# -V5.net
KiCad netlist of a schematic drawn in Altium Designer
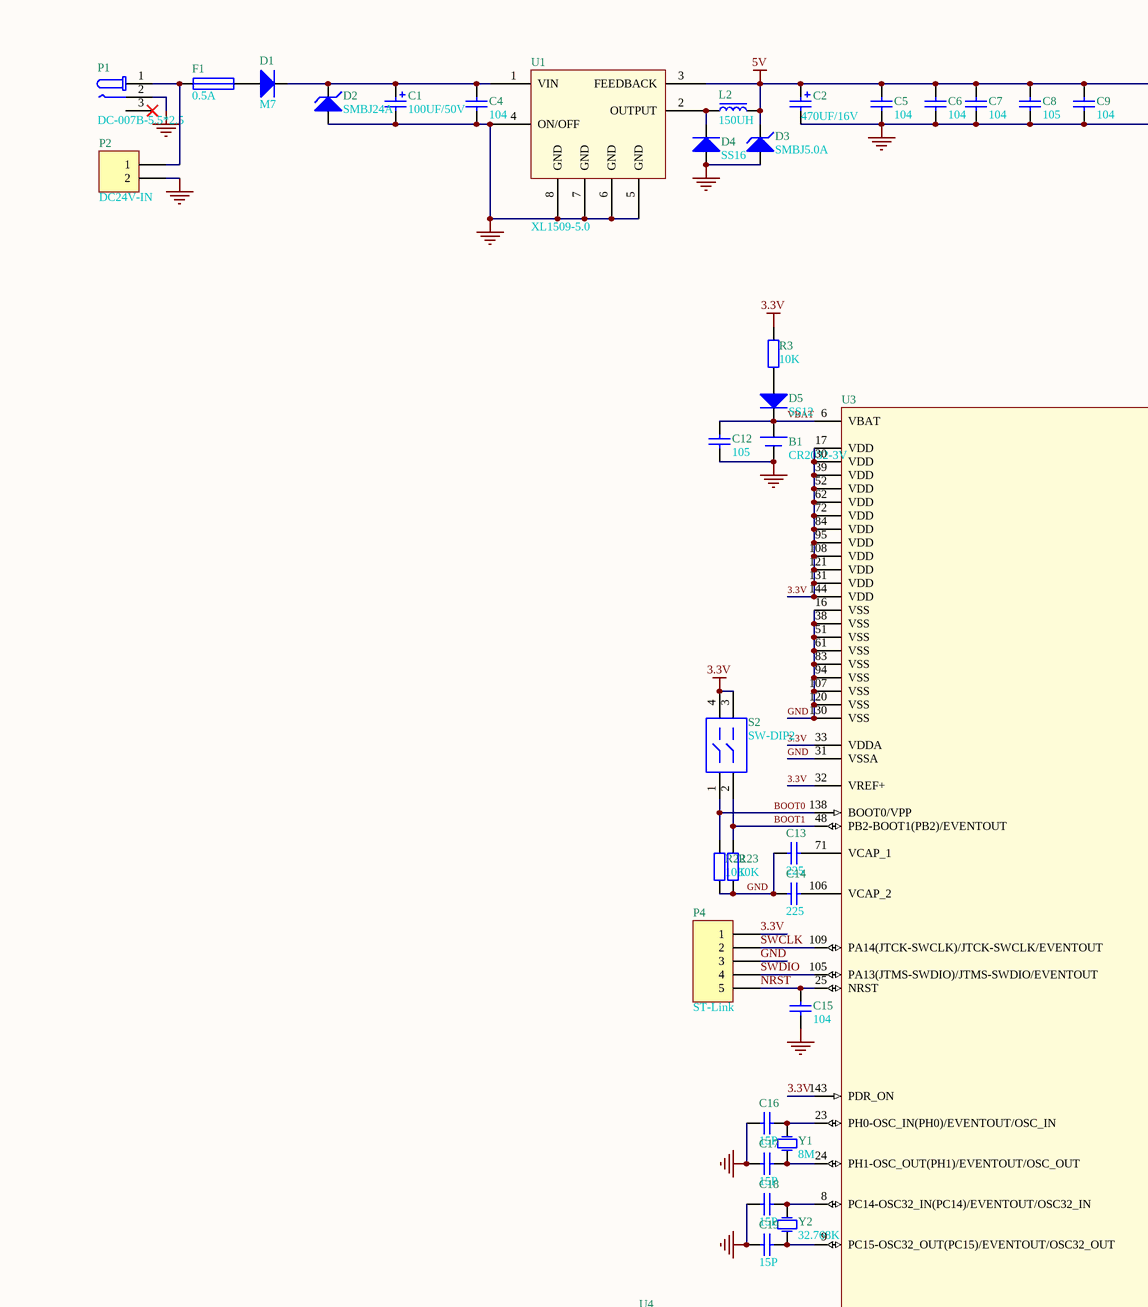
[diagram p0: 通讯转换模块-V5.SchDoc, top left]
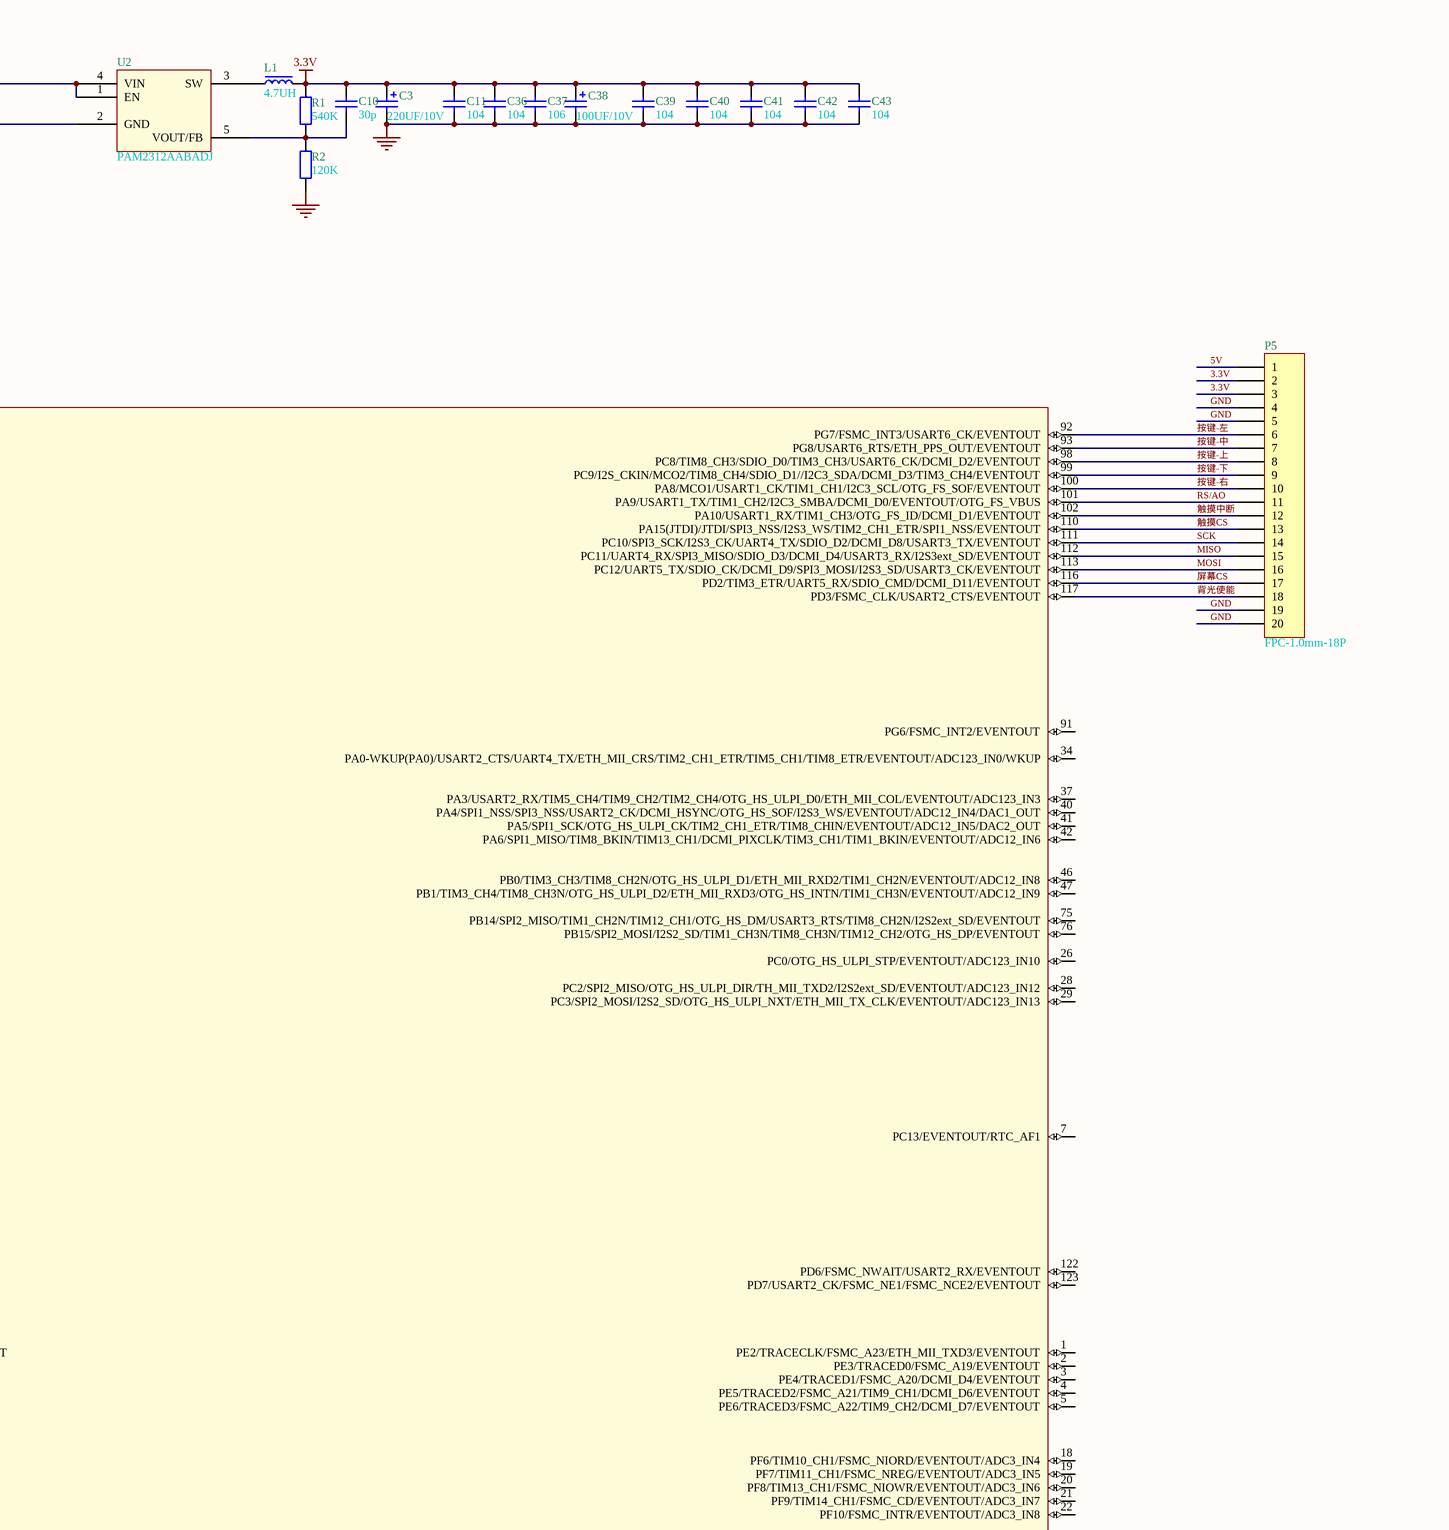
[diagram p1: 通讯转换模块-V5.SchDoc, top right]
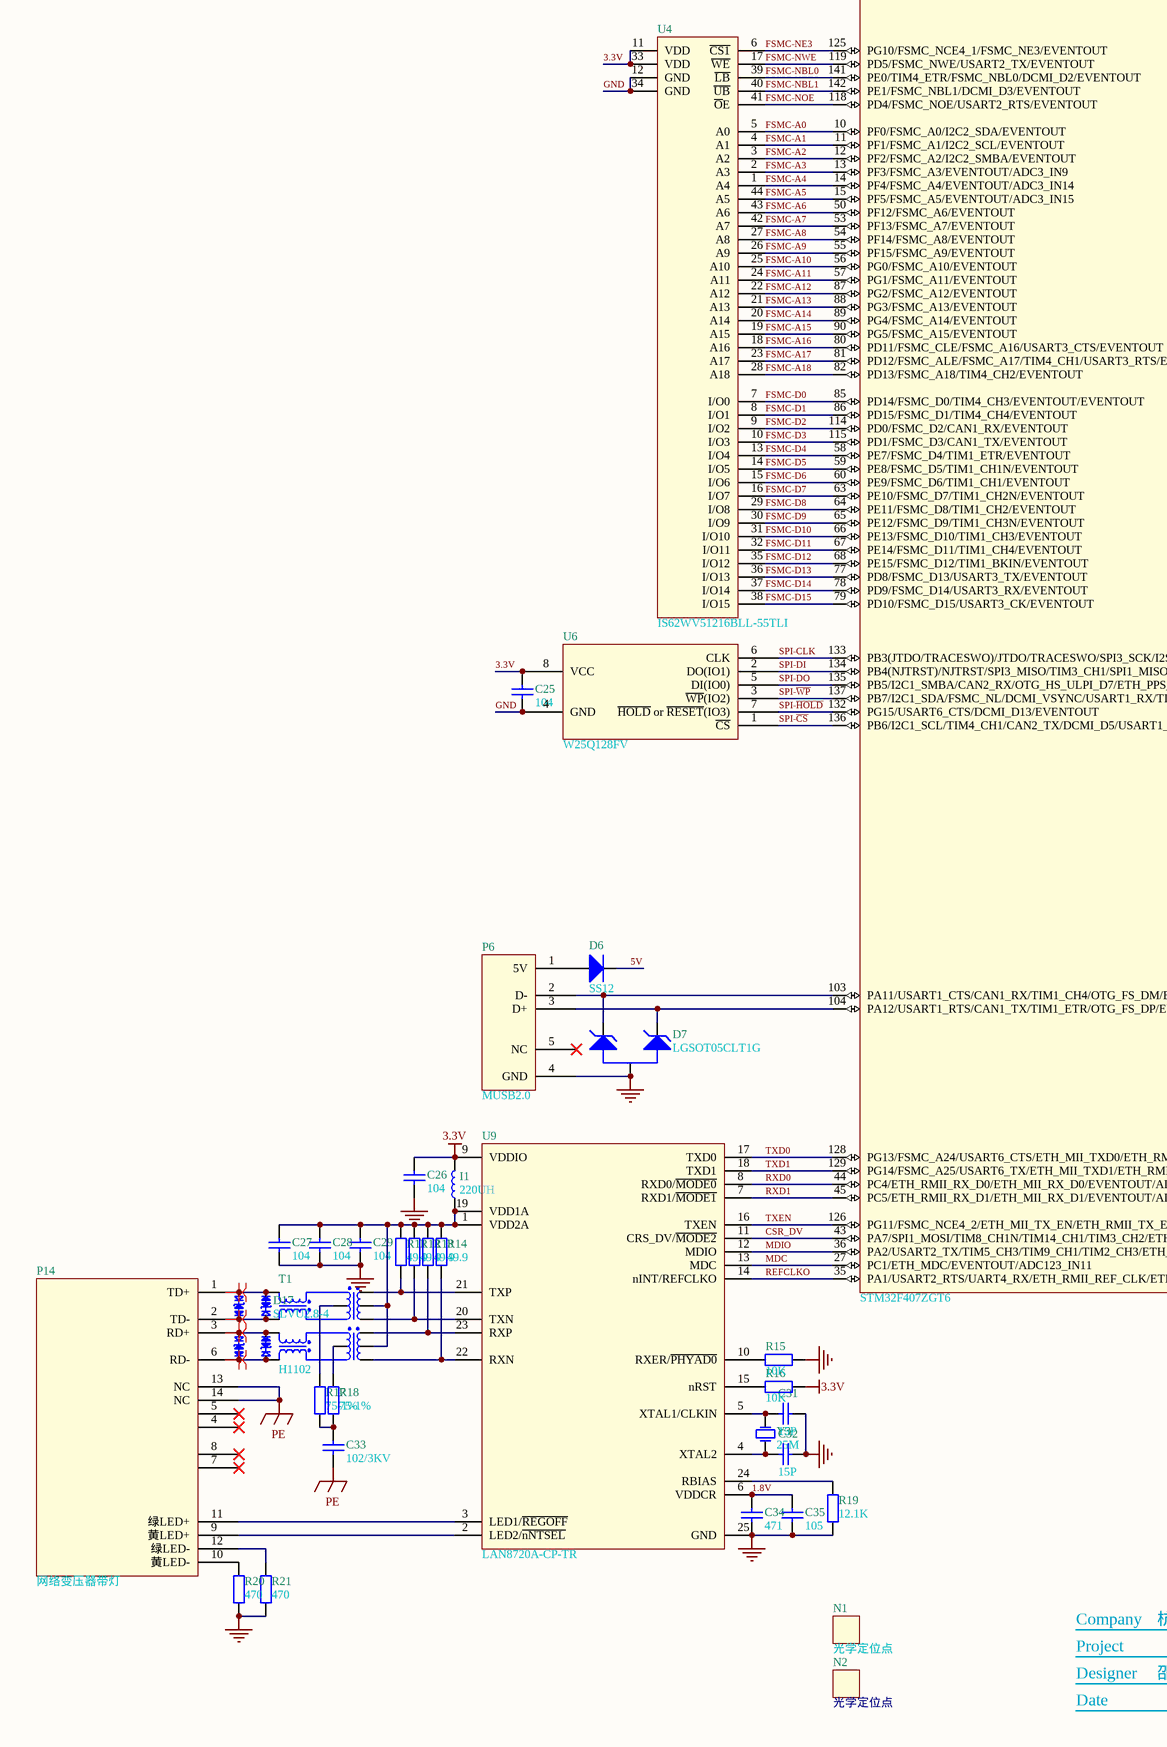
[diagram p2: 通讯转换模块-V5.SchDoc, bottom left]
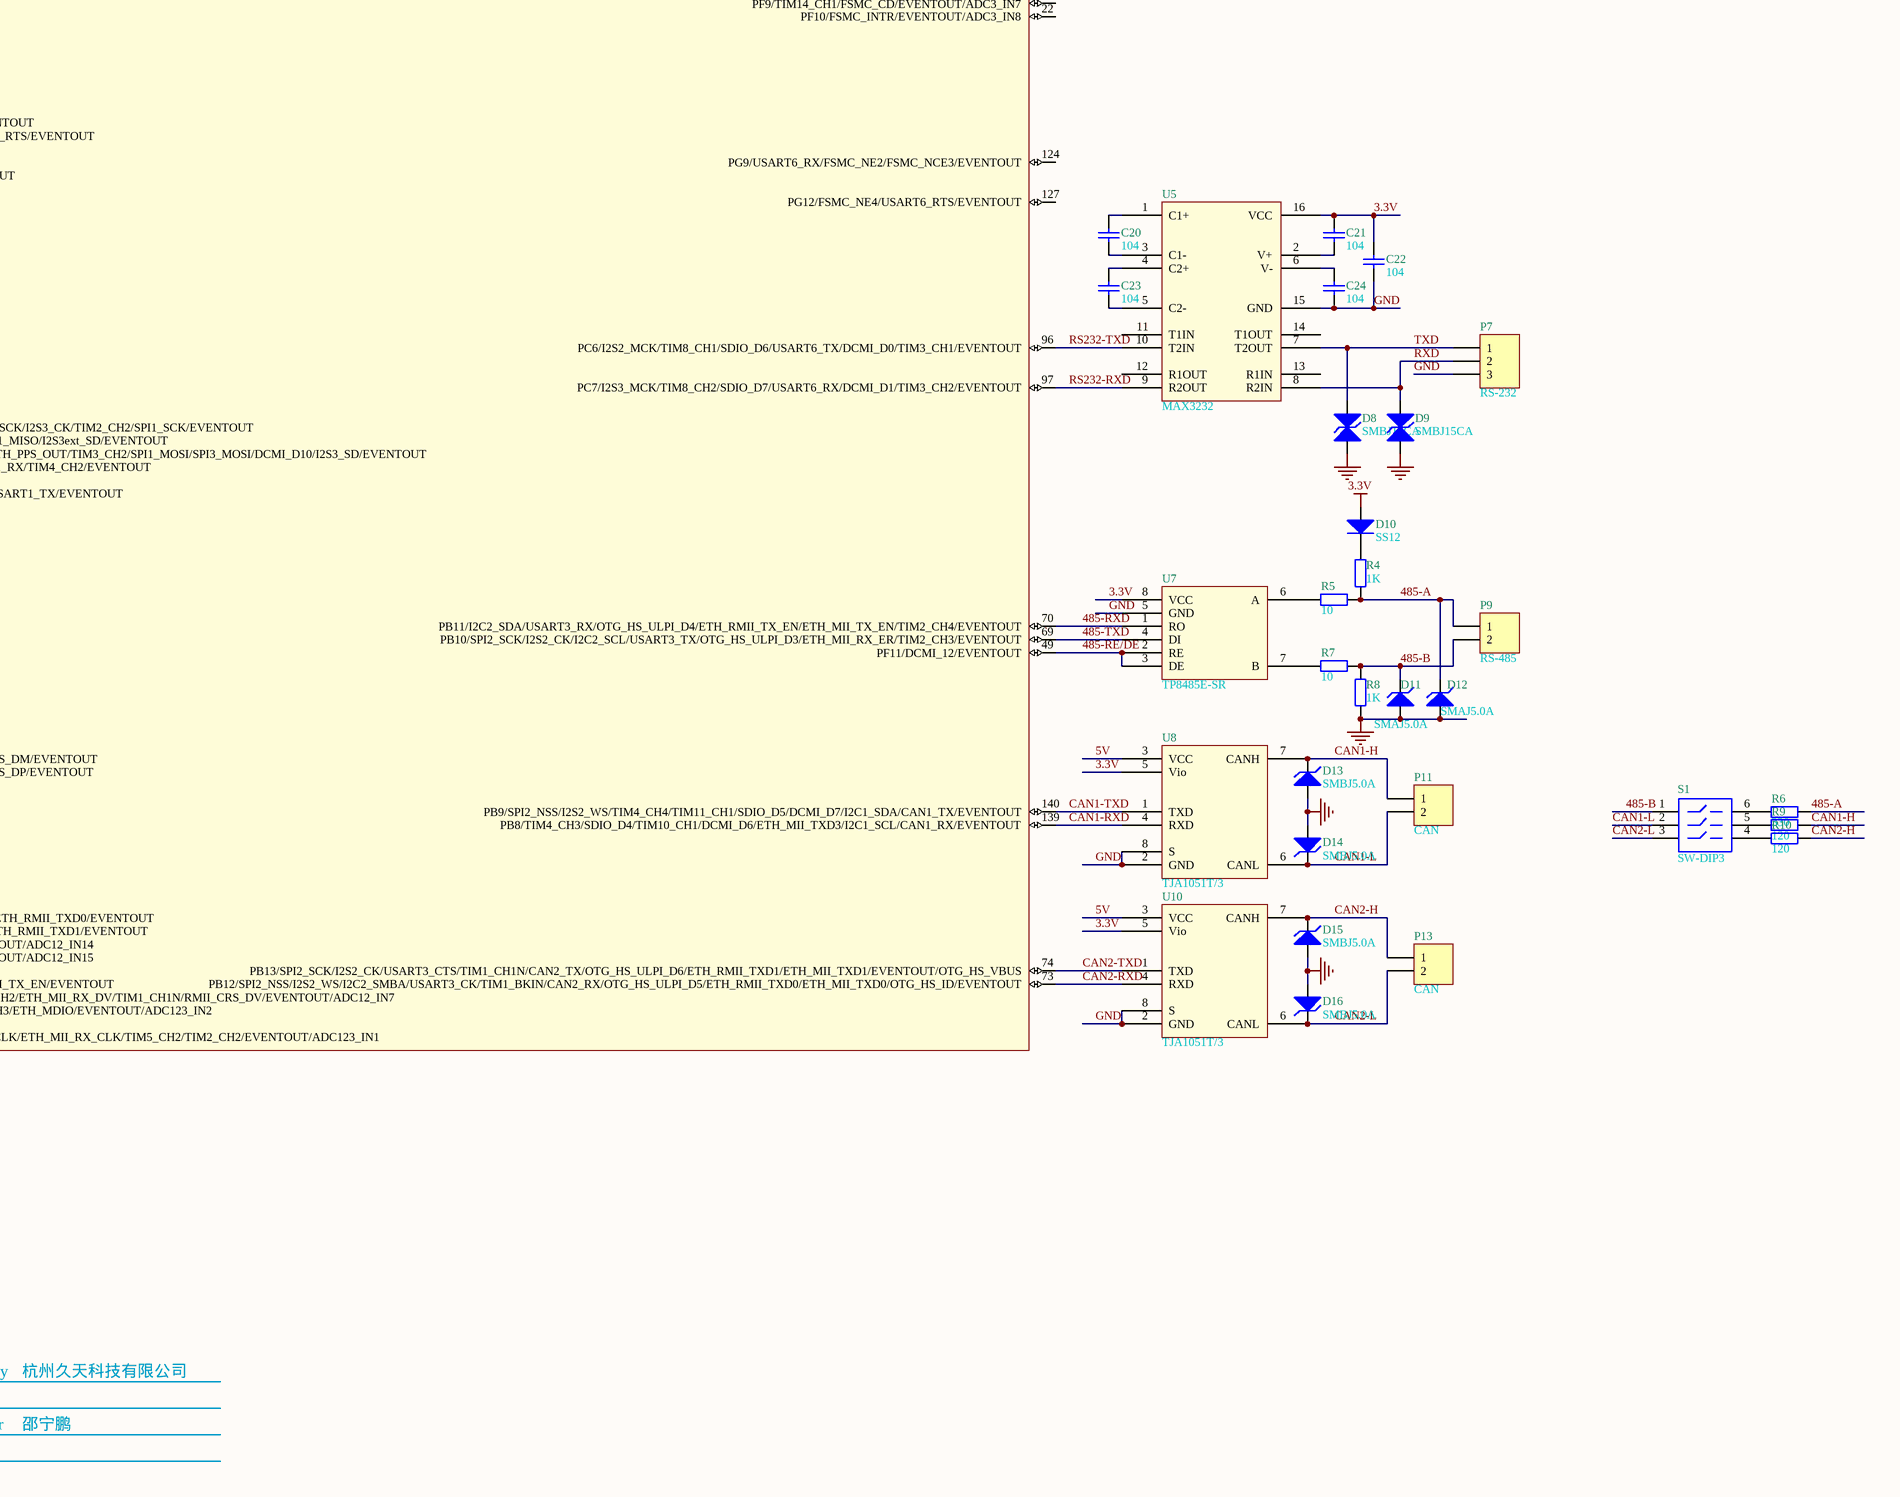
[diagram p3: 通讯转换模块-V5.SchDoc, bottom right]

(export (version "E")
  (design (tool "Eeschema 10.0.6"))
  (components
    (comp (ref "B1")
      (value "CR2032-3V")
      (footprint "CR2032")
      (description "锂电池")
      (libsource (lib "11其他元件-V1.0") (part "Battery1"))
    )
    (comp (ref "C1")
      (value "100UF/50V")
      (footprint "贴片固态电容8*10")
      (description "电解电容")
      (fields (field (name "PUBLISHER") "Altium Limited"))
      (libsource (lib "2电容-V1.0") (part "Cap Pol1"))
    )
    (comp (ref "C2")
      (value "470UF/16V")
      (footprint "贴片固态电容8*10")
      (description "电解电容")
      (fields (field (name "PUBLISHER") "Altium Limited"))
      (libsource (lib "2电容-V1.0") (part "Cap Pol1"))
    )
    (comp (ref "C3")
      (value "220UF/10V")
      (footprint "贴片固态电容6.3*7.7")
      (description "电解电容")
      (fields (field (name "PUBLISHER") "Altium Limited"))
      (libsource (lib "2电容-V1.0") (part "Cap Pol1"))
    )
    (comp (ref "C4")
      (value "104")
      (footprint "C-0603")
      (description "0805")
      (fields (field (name "PUBLISHER") "Altium Limited"))
      (libsource (lib "2电容-V1.0") (part "Cap-0805"))
    )
    (comp (ref "C5")
      (value "104")
      (footprint "C-0603")
      (description "0805")
      (fields (field (name "PUBLISHER") "Altium Limited"))
      (libsource (lib "2电容-V1.0") (part "Cap-0805"))
    )
    (comp (ref "C6")
      (value "104")
      (footprint "C-0603")
      (description "0805")
      (fields (field (name "PUBLISHER") "Altium Limited"))
      (libsource (lib "2电容-V1.0") (part "Cap-0805"))
    )
    (comp (ref "C7")
      (value "104")
      (footprint "C-0603")
      (description "0805")
      (fields (field (name "PUBLISHER") "Altium Limited"))
      (libsource (lib "2电容-V1.0") (part "Cap-0805"))
    )
    (comp (ref "C8")
      (value "105")
      (footprint "C-0603")
      (description "0805")
      (fields (field (name "PUBLISHER") "Altium Limited"))
      (libsource (lib "2电容-V1.0") (part "Cap-0805"))
    )
    (comp (ref "C9")
      (value "104")
      (footprint "C-0603")
      (description "0805")
      (fields (field (name "PUBLISHER") "Altium Limited"))
      (libsource (lib "2电容-V1.0") (part "Cap-0805"))
    )
    (comp (ref "C10")
      (value "30p")
      (footprint "C-0603")
      (description "0805")
      (fields (field (name "PUBLISHER") "Altium Limited"))
      (libsource (lib "2电容-V1.0") (part "Cap-0805"))
    )
    (comp (ref "C11")
      (value "104")
      (footprint "C-0603")
      (description "0805")
      (fields (field (name "PUBLISHER") "Altium Limited"))
      (libsource (lib "2电容-V1.0") (part "Cap-0805"))
    )
    (comp (ref "C12")
      (value "105")
      (footprint "C-0603")
      (description "0805")
      (fields (field (name "PUBLISHER") "Altium Limited"))
      (libsource (lib "2电容-V1.0") (part "Cap-0603"))
    )
    (comp (ref "C13")
      (value "225")
      (footprint "C-0603")
      (description "0805")
      (fields (field (name "PUBLISHER") "Altium Limited"))
      (libsource (lib "2电容-V1.0") (part "Cap-0603"))
    )
    (comp (ref "C14")
      (value "225")
      (footprint "C-0603")
      (description "0805")
      (fields (field (name "PUBLISHER") "Altium Limited"))
      (libsource (lib "2电容-V1.0") (part "Cap-0603"))
    )
    (comp (ref "C15")
      (value "104")
      (footprint "C-0603")
      (description "0805")
      (fields (field (name "PUBLISHER") "Altium Limited"))
      (libsource (lib "2电容-V1.0") (part "Cap-0603"))
    )
    (comp (ref "C16")
      (value "15P")
      (footprint "C-0603")
      (description "0805")
      (fields (field (name "PUBLISHER") "Altium Limited"))
      (libsource (lib "2电容-V1.0") (part "Cap-0603"))
    )
    (comp (ref "C17")
      (value "15P")
      (footprint "C-0603")
      (description "0805")
      (fields (field (name "PUBLISHER") "Altium Limited"))
      (libsource (lib "2电容-V1.0") (part "Cap-0603"))
    )
    (comp (ref "C18")
      (value "15P")
      (footprint "C-0603")
      (description "0805")
      (fields (field (name "PUBLISHER") "Altium Limited"))
      (libsource (lib "2电容-V1.0") (part "Cap-0603"))
    )
    (comp (ref "C19")
      (value "15P")
      (footprint "C-0603")
      (description "0805")
      (fields (field (name "PUBLISHER") "Altium Limited"))
      (libsource (lib "2电容-V1.0") (part "Cap-0603"))
    )
    (comp (ref "C20")
      (value "104")
      (footprint "C-0603")
      (description "0805")
      (fields (field (name "PUBLISHER") "Altium Limited"))
      (libsource (lib "2电容-V1.0") (part "Cap-0805"))
    )
    (comp (ref "C21")
      (value "104")
      (footprint "C-0603")
      (description "0805")
      (fields (field (name "PUBLISHER") "Altium Limited"))
      (libsource (lib "2电容-V1.0") (part "Cap-0805"))
    )
    (comp (ref "C22")
      (value "104")
      (footprint "C-0603")
      (description "0805")
      (fields (field (name "PUBLISHER") "Altium Limited"))
      (libsource (lib "2电容-V1.0") (part "Cap-0805"))
    )
    (comp (ref "C23")
      (value "104")
      (footprint "C-0603")
      (description "0805")
      (fields (field (name "PUBLISHER") "Altium Limited"))
      (libsource (lib "2电容-V1.0") (part "Cap-0805"))
    )
    (comp (ref "C24")
      (value "104")
      (footprint "C-0603")
      (description "0805")
      (fields (field (name "PUBLISHER") "Altium Limited"))
      (libsource (lib "2电容-V1.0") (part "Cap-0805"))
    )
    (comp (ref "C25")
      (value "104")
      (footprint "C-0603")
      (description "0805")
      (fields (field (name "PUBLISHER") "Altium Limited"))
      (libsource (lib "2电容-V1.0") (part "Cap-0603"))
    )
    (comp (ref "C26")
      (value "104")
      (footprint "C-0603")
      (description "0805")
      (fields (field (name "PUBLISHER") "Altium Limited"))
      (libsource (lib "2电容-V1.0") (part "Cap-0603"))
    )
    (comp (ref "C27")
      (value "104")
      (footprint "C-0603")
      (description "0805")
      (fields (field (name "PUBLISHER") "Altium Limited"))
      (libsource (lib "2电容-V1.0") (part "Cap-0603"))
    )
    (comp (ref "C28")
      (value "104")
      (footprint "C-0603")
      (description "0805")
      (fields (field (name "PUBLISHER") "Altium Limited"))
      (libsource (lib "2电容-V1.0") (part "Cap-0603"))
    )
    (comp (ref "C29")
      (value "104")
      (footprint "C-0603")
      (description "0805")
      (fields (field (name "PUBLISHER") "Altium Limited"))
      (libsource (lib "2电容-V1.0") (part "Cap-0603"))
    )
    (comp (ref "C31")
      (value "15P")
      (footprint "C-0603")
      (description "0805")
      (fields (field (name "PUBLISHER") "Altium Limited"))
      (libsource (lib "2电容-V1.0") (part "Cap-0603"))
    )
    (comp (ref "C32")
      (value "15P")
      (footprint "C-0603")
      (description "0805")
      (fields (field (name "PUBLISHER") "Altium Limited"))
      (libsource (lib "2电容-V1.0") (part "Cap-0603"))
    )
    (comp (ref "C33")
      (value "102/3KV")
      (footprint "C-1206")
      (description "0805")
      (fields (field (name "PUBLISHER") "Altium Limited"))
      (libsource (lib "2电容-V1.0") (part "Cap-0805"))
    )
    (comp (ref "C34")
      (value "471")
      (footprint "C-0603")
      (description "0805")
      (fields (field (name "PUBLISHER") "Altium Limited"))
      (libsource (lib "2电容-V1.0") (part "Cap-0603"))
    )
    (comp (ref "C35")
      (value "105")
      (footprint "C-0603")
      (description "0805")
      (fields (field (name "PUBLISHER") "Altium Limited"))
      (libsource (lib "2电容-V1.0") (part "Cap-0603"))
    )
    (comp (ref "C36")
      (value "104")
      (footprint "C-0603")
      (description "0805")
      (fields (field (name "PUBLISHER") "Altium Limited"))
      (libsource (lib "2电容-V1.0") (part "Cap-0805"))
    )
    (comp (ref "C37")
      (value "106")
      (footprint "C-0603")
      (description "0805")
      (fields (field (name "PUBLISHER") "Altium Limited"))
      (libsource (lib "2电容-V1.0") (part "Cap-0805"))
    )
    (comp (ref "C38")
      (value "100UF/10V")
      (footprint "贴片固态电容5*5.3")
      (description "电解电容")
      (fields (field (name "PUBLISHER") "Altium Limited"))
      (libsource (lib "2电容-V1.0") (part "Cap Pol1"))
    )
    (comp (ref "C39")
      (value "104")
      (footprint "C-0603")
      (description "0805")
      (fields (field (name "PUBLISHER") "Altium Limited"))
      (libsource (lib "2电容-V1.0") (part "Cap-0805"))
    )
    (comp (ref "C40")
      (value "104")
      (footprint "C-0603")
      (description "0805")
      (fields (field (name "PUBLISHER") "Altium Limited"))
      (libsource (lib "2电容-V1.0") (part "Cap-0805"))
    )
    (comp (ref "C41")
      (value "104")
      (footprint "C-0603")
      (description "0805")
      (fields (field (name "PUBLISHER") "Altium Limited"))
      (libsource (lib "2电容-V1.0") (part "Cap-0805"))
    )
    (comp (ref "C42")
      (value "104")
      (footprint "C-0603")
      (description "0805")
      (fields (field (name "PUBLISHER") "Altium Limited"))
      (libsource (lib "2电容-V1.0") (part "Cap-0805"))
    )
    (comp (ref "C43")
      (value "104")
      (footprint "C-0603")
      (description "0805")
      (fields (field (name "PUBLISHER") "Altium Limited"))
      (libsource (lib "2电容-V1.0") (part "Cap-0805"))
    )
    (comp (ref "D1")
      (value "M7")
      (footprint "SMA")
      (description "SMA")
      (fields (field (name "PUBLISHER") "Altium Limited"))
      (libsource (lib "4二极管-V1.1") (part "M7"))
    )
    (comp (ref "D2")
      (value "SMBJ24A")
      (footprint "SMB")
      (description "SMB")
      (libsource (lib "4二极管-V1.1") (part "TVS-1"))
    )
    (comp (ref "D3")
      (value "SMBJ5.0A")
      (footprint "SMB")
      (description "SMB")
      (libsource (lib "4二极管-V1.1") (part "TVS-1"))
    )
    (comp (ref "D4")
      (value "SS16")
      (footprint "SMA")
      (description "SMA")
      (libsource (lib "4二极管-V1.1") (part "SS14"))
    )
    (comp (ref "D5")
      (value "SS12")
      (footprint "sma")
      (description "SMA")
      (libsource (lib "4二极管-V1.1") (part "SS14"))
    )
    (comp (ref "D6")
      (value "SS12")
      (footprint "SMA")
      (description "SMA")
      (libsource (lib "4二极管-V1.1") (part "SS14"))
    )
    (comp (ref "D7")
      (value "LGSOT05CLT1G")
      (footprint "SOT-23")
      (description "ESD")
      (libsource (lib "4二极管-V1.1") (part "ESDA5V3L"))
    )
    (comp (ref "D8")
      (value "SMBJ15CA")
      (footprint "SMB无极性")
      (description "SMB")
      (libsource (lib "4二极管-V1.1") (part "TVS-2"))
    )
    (comp (ref "D9")
      (value "SMBJ15CA")
      (footprint "SMB无极性")
      (description "SMB")
      (libsource (lib "4二极管-V1.1") (part "TVS-2"))
    )
    (comp (ref "D10")
      (value "SS12")
      (footprint "SMA")
      (description "SMA")
      (libsource (lib "4二极管-V1.1") (part "SS14"))
    )
    (comp (ref "D11")
      (value "SMAJ5.0A")
      (footprint "SMB-N")
      (description "SMB")
      (libsource (lib "4二极管-V1.1") (part "TVS-1"))
    )
    (comp (ref "D12")
      (value "SMAJ5.0A")
      (footprint "SMB-N")
      (description "SMB")
      (libsource (lib "4二极管-V1.1") (part "TVS-1"))
    )
    (comp (ref "D13")
      (value "SMBJ5.0A")
      (footprint "SMB-N")
      (description "SMB")
      (libsource (lib "4二极管-V1.1") (part "TVS-1"))
    )
    (comp (ref "D14")
      (value "SMBJ5.0A")
      (footprint "SMB-N")
      (description "SMB")
      (libsource (lib "4二极管-V1.1") (part "TVS-1"))
    )
    (comp (ref "D15")
      (value "SMBJ5.0A")
      (footprint "SMB-N")
      (description "SMB")
      (libsource (lib "4二极管-V1.1") (part "TVS-1"))
    )
    (comp (ref "D16")
      (value "SMBJ5.0A")
      (footprint "SMB-N")
      (description "SMB")
      (libsource (lib "4二极管-V1.1") (part "TVS-1"))
    )
    (comp (ref "D17")
      (value "SLVU2.8-4")
      (footprint "SOP-8-N")
      (libsource (lib "4二极管-V1.1") (part "SLVU2.8-4"))
    )
    (comp (ref "F1")
      (value "0.5A")
      (footprint "FUSE-1808")
      (description "Fuse")
      (fields (field (name "PUBLISHER") "Altium Limited"))
      (libsource (lib "11其他元件-V1.0") (part "Fuse 1"))
    )
    (comp (ref "I1") (value "220UH") (footprint "CD32") (libsource (lib "3电感-V1.0") (part "Inductance1")))
    (comp (ref "L1") (value "4.7UH") (footprint "CD54") (libsource (lib "3电感-V1.0") (part "Inductance3")))
    (comp (ref "L2") (value "150UH") (footprint "CD75") (libsource (lib "3电感-V1.0") (part "Inductance3")))
    (comp (ref "N1") (value "光学定位点") (footprint "MARK-1mm-3mm") (libsource (lib "11其他元件-V1.0") (part "无引脚")))
    (comp (ref "N2") (value "光学定位点") (footprint "MARK-1mm-3mm") (libsource (lib "11其他元件-V1.0") (part "无引脚")))
    (comp (ref "P1")
      (value "DC-007B-5.5*2.5")
      (footprint "DC-007B")
      (libsource (lib "PJ系列") (part "DC-007B"))
    )
    (comp (ref "P2")
      (value "DC24V-IN")
      (footprint "KF2EDG5.08V-2P-有挡边-卧式")
      (description "Header, 2-Pin")
      (fields (field (name "PUBLISHER") "Altium Limited"))
      (libsource (lib "") (part "Header 2_1"))
    )
    (comp (ref "P4")
      (value "ST-Link")
      (footprint "HDR1X5")
      (description "Header, 5-Pin")
      (fields (field (name "PUBLISHER") "Altium Limited"))
      (libsource (lib "5排针-V1.0") (part "Header 5"))
    )
    (comp (ref "P5")
      (value "FPC-1.0mm-18P")
      (footprint "FPC-1.0mm_18P下接翻盖")
      (description "Header, 20-Pin")
      (fields (field (name "PUBLISHER") "Altium Limited"))
      (libsource (lib "5排针-V1.0") (part "Header 20"))
    )
    (comp (ref "P6")
      (value "MUSB2.0")
      (footprint "USB1.1-插件-母座")
      (libsource (lib "11其他元件-V1.0") (part "USB-4_A"))
    )
    (comp (ref "P7")
      (value "RS-232")
      (footprint "KF2EDG5.08V-3P-有挡边-卧式")
      (description "Header, 3-Pin")
      (fields (field (name "PUBLISHER") "Altium Limited"))
      (libsource (lib "5排针-V1.0") (part "Header 3"))
    )
    (comp (ref "P9")
      (value "RS-485")
      (footprint "KF2EDG5.08V-2P-有挡边-卧式")
      (description "Header, 2-Pin")
      (fields (field (name "PUBLISHER") "Altium Limited"))
      (libsource (lib "5排针-V1.0") (part "Header 2"))
    )
    (comp (ref "P11")
      (value "CAN")
      (footprint "KF2EDG5.08V-2P-有挡边-卧式")
      (description "Header, 2-Pin")
      (fields (field (name "PUBLISHER") "Altium Limited"))
      (libsource (lib "5排针-V1.0") (part "Header 2"))
    )
    (comp (ref "P13")
      (value "CAN")
      (footprint "KF2EDG5.08V-2P-有挡边-卧式")
      (description "Header, 2-Pin")
      (fields (field (name "PUBLISHER") "Altium Limited"))
      (libsource (lib "5排针-V1.0") (part "Header 2"))
    )
    (comp (ref "P14")
      (value "网络变压器带灯")
      (footprint "RJ45-8P8C-56带灯")
      (libsource (lib "11其他元件-V1.0") (part "网络变压器带灯"))
    )
    (comp (ref "R1")
      (value "540K")
      (footprint "R-0603")
      (description "0603")
      (fields (field (name "PUBLISHER") "Altium Limited"))
      (libsource (lib "1电阻-V1.0") (part "Res2-0603"))
    )
    (comp (ref "R2")
      (value "120K")
      (footprint "R-0603")
      (description "0603")
      (fields (field (name "PUBLISHER") "Altium Limited"))
      (libsource (lib "1电阻-V1.0") (part "Res2-0603"))
    )
    (comp (ref "R3")
      (value "10K")
      (footprint "R-0603")
      (description "0603")
      (fields (field (name "PUBLISHER") "Altium Limited"))
      (libsource (lib "1电阻-V1.0") (part "Res2-0603"))
    )
    (comp (ref "R4")
      (value "1K")
      (footprint "R-0603")
      (description "Resistor")
      (fields (field (name "PUBLISHER") "Altium Limited"))
      (libsource (lib "") (part "Res2_2"))
    )
    (comp (ref "R5")
      (value "10")
      (footprint "R-0805")
      (description "Resistor")
      (fields (field (name "PUBLISHER") "Altium Limited"))
      (libsource (lib "Miscellaneous Devices") (part "Res2"))
    )
    (comp (ref "R6")
      (value "330")
      (footprint "R-1206")
      (description "Resistor")
      (fields (field (name "PUBLISHER") "Altium Limited"))
      (libsource (lib "Miscellaneous Devices") (part "Res2"))
    )
    (comp (ref "R7")
      (value "10")
      (footprint "R-0805")
      (description "Resistor")
      (fields (field (name "PUBLISHER") "Altium Limited"))
      (libsource (lib "Miscellaneous Devices") (part "Res2"))
    )
    (comp (ref "R8")
      (value "1K")
      (footprint "R-0603")
      (description "Resistor")
      (fields (field (name "PUBLISHER") "Altium Limited"))
      (libsource (lib "元件2.0") (part "Res2"))
    )
    (comp (ref "R9")
      (value "120")
      (footprint "R-1206")
      (description "Resistor")
      (fields (field (name "PUBLISHER") "Altium Limited"))
      (libsource (lib "Miscellaneous Devices") (part "Res2"))
    )
    (comp (ref "R10")
      (value "120")
      (footprint "R-1206")
      (description "Resistor")
      (fields (field (name "PUBLISHER") "Altium Limited"))
      (libsource (lib "Miscellaneous Devices") (part "Res2"))
    )
    (comp (ref "R11")
      (value "49.9")
      (footprint "R-0603")
      (description "Resistor")
      (fields (field (name "PUBLISHER") "Altium Limited"))
      (libsource (lib "") (part "Res2_1"))
    )
    (comp (ref "R12")
      (value "49.9")
      (footprint "R-0603")
      (description "Resistor")
      (fields (field (name "PUBLISHER") "Altium Limited"))
      (libsource (lib "") (part "Res2_1"))
    )
    (comp (ref "R13")
      (value "49.9")
      (footprint "R-0603")
      (description "Resistor")
      (fields (field (name "PUBLISHER") "Altium Limited"))
      (libsource (lib "") (part "Res2_1"))
    )
    (comp (ref "R14")
      (value "49.9")
      (footprint "R-0603")
      (description "Resistor")
      (fields (field (name "PUBLISHER") "Altium Limited"))
      (libsource (lib "") (part "Res2_1"))
    )
    (comp (ref "R15")
      (value "10K")
      (footprint "R-0603")
      (description "0603")
      (fields (field (name "PUBLISHER") "Altium Limited"))
      (libsource (lib "") (part "Res2-0603_2"))
    )
    (comp (ref "R16")
      (value "10K")
      (footprint "R-0603")
      (description "0603")
      (fields (field (name "PUBLISHER") "Altium Limited"))
      (libsource (lib "") (part "Res2-0603_2"))
    )
    (comp (ref "R17")
      (value "75-1%")
      (footprint "R-0603")
      (description "0805")
      (fields (field (name "PUBLISHER") "Altium Limited"))
      (libsource (lib "1电阻-V1.0") (part "Res2-0805"))
    )
    (comp (ref "R18")
      (value "75-1%")
      (footprint "R-0603")
      (description "0805")
      (fields (field (name "PUBLISHER") "Altium Limited"))
      (libsource (lib "") (part "Res2-0805_1"))
    )
    (comp (ref "R19")
      (value "12.1K")
      (footprint "R-0603")
      (description "0603")
      (fields (field (name "PUBLISHER") "Altium Limited"))
      (libsource (lib "") (part "Res2-0603_1"))
    )
    (comp (ref "R20")
      (value "470")
      (footprint "R-0603")
      (description "0603")
      (fields (field (name "PUBLISHER") "Altium Limited"))
      (libsource (lib "") (part "Res2-0603_1"))
    )
    (comp (ref "R21")
      (value "470")
      (footprint "R-0603")
      (description "0603")
      (fields (field (name "PUBLISHER") "Altium Limited"))
      (libsource (lib "1电阻-V1.0") (part "Res2-0603"))
    )
    (comp (ref "R22")
      (value "10K")
      (footprint "R-0603")
      (description "0603")
      (fields (field (name "PUBLISHER") "Altium Limited"))
      (libsource (lib "1电阻-V1.0") (part "Res2-0603"))
    )
    (comp (ref "R23")
      (value "10K")
      (footprint "R-0603")
      (description "0603")
      (fields (field (name "PUBLISHER") "Altium Limited"))
      (libsource (lib "1电阻-V1.0") (part "Res2-0603"))
    )
    (comp (ref "S1")
      (value "SW-DIP3")
      (footprint "SW-红色拨码开关-侧拨弯脚3P")
      (fields (field (name "PUBLISHER") "Altium Limited"))
      (libsource (lib "开关-V1") (part "SW-DIP3"))
    )
    (comp (ref "S2")
      (value "SW-DIP2")
      (footprint "SW-红色拨码开关2P")
      (fields (field (name "PUBLISHER") "Altium Limited"))
      (libsource (lib "开关-V1") (part "SW-DIP2"))
    )
    (comp (ref "T1") (value "H1102") (footprint "H1102") (libsource (lib "3电感-V1.0") (part "H1102")))
    (comp (ref "U1")
      (value "XL1509-5.0")
      (footprint "SOP-8-m")
      (description "开关电源 SOP-8")
      (libsource (lib "8集成电路-V1.1") (part "XL1509-ADJ"))
    )
    (comp (ref "U2")
      (value "PAM2312AABADJ")
      (footprint "SOT-23-5-M")
      (description "开关电源 SOT-23-5")
      (libsource (lib "电源芯片DC-DC") (part "PAM2312"))
    )
    (comp (ref "U3")
      (value "STM32F407ZGT6")
      (footprint "TQFP-144-L")
      (libsource (lib "9单片机-V1.0") (part "STM32F407ZET6"))
    )
    (comp (ref "U4")
      (value "IS62WV51216BLL-55TLI")
      (footprint "TSOP2-44-L")
      (libsource (lib "存储") (part "IS62WV51216BLL-55TLI"))
    )
    (comp (ref "U5") (value "MAX3232") (footprint "SOP-16-M") (libsource (lib "8集成电路-V1.1") (part "MAX3232")))
    (comp (ref "U6")
      (value "W25Q128FV")
      (footprint "SOIC-8-M")
      (description "SPI-FLASH")
      (libsource (lib "8集成电路-V1.1") (part "W25Q128FV"))
    )
    (comp (ref "U7")
      (value "TP8485E-SR")
      (footprint "SOP-8-N")
      (description "RS485总线转串口")
      (libsource (lib "集成电路1.0") (part "MAX3082"))
    )
    (comp (ref "U8") (value "TJA1051T/3") (footprint "SOP-8-N") (libsource (lib "通讯-V1") (part "TJA1051T/3")))
    (comp (ref "U9")
      (value "LAN8720A-CP-TR")
      (footprint "QFN-24")
      (description "以太网PHY")
      (libsource (lib "通讯-V1") (part "LAN8720A-CP-TR"))
    )
    (comp (ref "U10")
      (value "TJA1051T/3")
      (footprint "SOP-8-N")
      (libsource (lib "通讯-V1") (part "TJA1051T/3"))
    )
    (comp (ref "Y1") (value "8M") (footprint "HC-49SMD") (libsource (lib "11其他元件-V1.0") (part "晶振")))
    (comp (ref "Y2") (value "32.768K") (footprint "FC135") (libsource (lib "11其他元件-V1.0") (part "晶振")))
    (comp (ref "Y3") (value "25M") (footprint "HC-49SMD") (libsource (lib "11其他元件-V1.0") (part "晶振")))
  )
  (nets
    (net (code "1") (name "/1.8V") (class "Default")
      (node (ref "C34") (pin "2") (pinfunction "2_2") (pintype "passive"))
      (node (ref "C35") (pin "2") (pinfunction "2_2") (pintype "passive"))
      (node (ref "U9") (pin "6") (pinfunction "VDDCR_6") (pintype "passive"))
    )
    (net (code "2") (name "/485-A") (class "Default")
      (node (ref "D12") (pin "2") (pinfunction "K_2") (pintype "passive"))
      (node (ref "P9") (pin "1") (pinfunction "1_1") (pintype "passive"))
      (node (ref "R4") (pin "2") (pinfunction "2_2") (pintype "passive"))
      (node (ref "R5") (pin "1") (pinfunction "1_1") (pintype "passive"))
      (node (ref "R6") (pin "1") (pinfunction "1_1") (pintype "passive"))
    )
    (net (code "3") (name "/485-B") (class "Default")
      (node (ref "D11") (pin "2") (pinfunction "K_2") (pintype "passive"))
      (node (ref "P9") (pin "2") (pinfunction "2_2") (pintype "passive"))
      (node (ref "R7") (pin "1") (pinfunction "1_1") (pintype "passive"))
      (node (ref "R8") (pin "2") (pinfunction "2_2") (pintype "passive"))
      (node (ref "S1") (pin "1") (pinfunction "1_1") (pintype "passive"))
    )
    (net (code "4") (name "/485-RE{slash}DE") (class "Default")
      (node (ref "U3") (pin "49") (pinfunction "PF11/DCMI_12/EVENTOUT_49") (pintype "bidirectional"))
      (node (ref "U7") (pin "2") (pinfunction "RE_2") (pintype "passive"))
      (node (ref "U7") (pin "3") (pinfunction "DE_3") (pintype "passive"))
    )
    (net (code "5") (name "/485-RXD") (class "Default")
      (node (ref "U3") (pin "70") (pinfunction "PB11/I2C2_SDA/USART3_RX/OTG_HS_ULPI_D4/ETH_RMII_TX_EN/ETH_MII_TX_EN/TIM2_CH4/EVENTOUT_70") (pintype "bidirectional"))
      (node (ref "U7") (pin "1") (pinfunction "RO_1") (pintype "passive"))
    )
    (net (code "6") (name "/485-TXD") (class "Default")
      (node (ref "U3") (pin "69") (pinfunction "PB10/SPI2_SCK/I2S2_CK/I2C2_SCL/USART3_TX/OTG_HS_ULPI_D3/ETH_MII_RX_ER/TIM2_CH3/EVENTOUT_69") (pintype "bidirectional"))
      (node (ref "U7") (pin "4") (pinfunction "DI_4") (pintype "passive"))
    )
    (net (code "7") (name "/BOOT0") (class "Default")
      (node (ref "R22") (pin "2") (pinfunction "2_2") (pintype "passive"))
      (node (ref "S2") (pin "1") (pinfunction "1_1") (pintype "passive"))
      (node (ref "U3") (pin "138") (pinfunction "BOOT0/VPP_138") (pintype "input"))
    )
    (net (code "8") (name "/BOOT1") (class "Default")
      (node (ref "R23") (pin "2") (pinfunction "2_2") (pintype "passive"))
      (node (ref "S2") (pin "2") (pinfunction "2_2") (pintype "passive"))
      (node (ref "U3") (pin "48") (pinfunction "PB2-BOOT1(PB2)/EVENTOUT_48") (pintype "bidirectional"))
    )
    (net (code "9") (name "/CAN1-H") (class "Default")
      (node (ref "D13") (pin "2") (pinfunction "K_2") (pintype "passive"))
      (node (ref "P11") (pin "1") (pinfunction "1_1") (pintype "passive"))
      (node (ref "R9") (pin "1") (pinfunction "1_1") (pintype "passive"))
      (node (ref "U8") (pin "7") (pinfunction "CANH_7") (pintype "passive"))
    )
    (net (code "10") (name "/CAN1-L") (class "Default")
      (node (ref "D14") (pin "2") (pinfunction "K_2") (pintype "passive"))
      (node (ref "P11") (pin "2") (pinfunction "2_2") (pintype "passive"))
      (node (ref "S1") (pin "2") (pinfunction "2_2") (pintype "passive"))
      (node (ref "U8") (pin "6") (pinfunction "CANL_6") (pintype "passive"))
    )
    (net (code "11") (name "/CAN1-RXD") (class "Default")
      (node (ref "U3") (pin "139") (pinfunction "PB8/TIM4_CH3/SDIO_D4/TIM10_CH1/DCMI_D6/ETH_MII_TXD3/I2C1_SCL/CAN1_RX/EVENTOUT_139") (pintype "bidirectional"))
      (node (ref "U8") (pin "4") (pinfunction "RXD_4") (pintype "passive"))
    )
    (net (code "12") (name "/CAN1-TXD") (class "Default")
      (node (ref "U3") (pin "140") (pinfunction "PB9/SPI2_NSS/I2S2_WS/TIM4_CH4/TIM11_CH1/SDIO_D5/DCMI_D7/I2C1_SDA/CAN1_TX/EVENTOUT_140") (pintype "bidirectional"))
      (node (ref "U8") (pin "1") (pinfunction "TXD_1") (pintype "passive"))
    )
    (net (code "13") (name "/CAN2-H") (class "Default")
      (node (ref "D15") (pin "2") (pinfunction "K_2") (pintype "passive"))
      (node (ref "P13") (pin "1") (pinfunction "1_1") (pintype "passive"))
      (node (ref "R10") (pin "1") (pinfunction "1_1") (pintype "passive"))
      (node (ref "U10") (pin "7") (pinfunction "CANH_7") (pintype "passive"))
    )
    (net (code "14") (name "/CAN2-L") (class "Default")
      (node (ref "D16") (pin "2") (pinfunction "K_2") (pintype "passive"))
      (node (ref "P13") (pin "2") (pinfunction "2_2") (pintype "passive"))
      (node (ref "S1") (pin "3") (pinfunction "3_3") (pintype "passive"))
      (node (ref "U10") (pin "6") (pinfunction "CANL_6") (pintype "passive"))
    )
    (net (code "15") (name "/CAN2-RXD") (class "Default")
      (node (ref "U10") (pin "4") (pinfunction "RXD_4") (pintype "passive"))
      (node (ref "U3") (pin "73") (pinfunction "PB12/SPI2_NSS/I2S2_WS/I2C2_SMBA/USART3_CK/TIM1_BKIN/CAN2_RX/OTG_HS_ULPI_D5/ETH_RMII_TXD0/ETH_MII_TXD0/OTG_HS_ID/EVENTOUT_73") (pintype "bidirectional"))
    )
    (net (code "16") (name "/CAN2-TXD") (class "Default")
      (node (ref "U10") (pin "1") (pinfunction "TXD_1") (pintype "passive"))
      (node (ref "U3") (pin "74") (pinfunction "PB13/SPI2_SCK/I2S2_CK/USART3_CTS/TIM1_CH1N/CAN2_TX/OTG_HS_ULPI_D6/ETH_RMII_TXD1/ETH_MII_TXD1/EVENTOUT/OTG_HS_VBUS_74") (pintype "bidirectional"))
    )
    (net (code "17") (name "/CSR_DV") (class "Default")
      (node (ref "U3") (pin "43") (pinfunction "PA7/SPI1_MOSI/TIM8_CH1N/TIM14_CH1/TIM3_CH2/ETH_MII_RX_DV/TIM1_CH1N/RMII_CRS_DV/EVENTOUT/ADC12_IN7_43") (pintype "bidirectional"))
      (node (ref "U9") (pin "11") (pinfunction "CRS_DV/~{MODE2}_11") (pintype "passive"))
    )
    (net (code "18") (name "/FSMC-A0") (class "Default")
      (node (ref "U3") (pin "10") (pinfunction "PF0/FSMC_A0/I2C2_SDA/EVENTOUT_10") (pintype "bidirectional"))
      (node (ref "U4") (pin "5") (pinfunction "A0_5") (pintype "passive"))
    )
    (net (code "19") (name "/FSMC-A1") (class "Default")
      (node (ref "U3") (pin "11") (pinfunction "PF1/FSMC_A1/I2C2_SCL/EVENTOUT_11") (pintype "bidirectional"))
      (node (ref "U4") (pin "4") (pinfunction "A1_4") (pintype "passive"))
    )
    (net (code "20") (name "/FSMC-A2") (class "Default")
      (node (ref "U3") (pin "12") (pinfunction "PF2/FSMC_A2/I2C2_SMBA/EVENTOUT_12") (pintype "bidirectional"))
      (node (ref "U4") (pin "3") (pinfunction "A2_3") (pintype "passive"))
    )
    (net (code "21") (name "/FSMC-A3") (class "Default")
      (node (ref "U3") (pin "13") (pinfunction "PF3/FSMC_A3/EVENTOUT/ADC3_IN9_13") (pintype "bidirectional"))
      (node (ref "U4") (pin "2") (pinfunction "A3_2") (pintype "passive"))
    )
    (net (code "22") (name "/FSMC-A4") (class "Default")
      (node (ref "U3") (pin "14") (pinfunction "PF4/FSMC_A4/EVENTOUT/ADC3_IN14_14") (pintype "bidirectional"))
      (node (ref "U4") (pin "1") (pinfunction "A4_1") (pintype "passive"))
    )
    (net (code "23") (name "/FSMC-A5") (class "Default")
      (node (ref "U3") (pin "15") (pinfunction "PF5/FSMC_A5/EVENTOUT/ADC3_IN15_15") (pintype "bidirectional"))
      (node (ref "U4") (pin "44") (pinfunction "A5_44") (pintype "passive"))
    )
    (net (code "24") (name "/FSMC-A6") (class "Default")
      (node (ref "U3") (pin "50") (pinfunction "PF12/FSMC_A6/EVENTOUT_50") (pintype "bidirectional"))
      (node (ref "U4") (pin "43") (pinfunction "A6_43") (pintype "passive"))
    )
    (net (code "25") (name "/FSMC-A7") (class "Default")
      (node (ref "U3") (pin "53") (pinfunction "PF13/FSMC_A7/EVENTOUT_53") (pintype "bidirectional"))
      (node (ref "U4") (pin "42") (pinfunction "A7_42") (pintype "passive"))
    )
    (net (code "26") (name "/FSMC-A8") (class "Default")
      (node (ref "U3") (pin "54") (pinfunction "PF14/FSMC_A8/EVENTOUT_54") (pintype "bidirectional"))
      (node (ref "U4") (pin "27") (pinfunction "A8_27") (pintype "passive"))
    )
    (net (code "27") (name "/FSMC-A9") (class "Default")
      (node (ref "U3") (pin "55") (pinfunction "PF15/FSMC_A9/EVENTOUT_55") (pintype "bidirectional"))
      (node (ref "U4") (pin "26") (pinfunction "A9_26") (pintype "passive"))
    )
    (net (code "28") (name "/FSMC-A10") (class "Default")
      (node (ref "U3") (pin "56") (pinfunction "PG0/FSMC_A10/EVENTOUT_56") (pintype "bidirectional"))
      (node (ref "U4") (pin "25") (pinfunction "A10_25") (pintype "passive"))
    )
    (net (code "29") (name "/FSMC-A11") (class "Default")
      (node (ref "U3") (pin "57") (pinfunction "PG1/FSMC_A11/EVENTOUT_57") (pintype "bidirectional"))
      (node (ref "U4") (pin "24") (pinfunction "A11_24") (pintype "passive"))
    )
    (net (code "30") (name "/FSMC-A12") (class "Default")
      (node (ref "U3") (pin "87") (pinfunction "PG2/FSMC_A12/EVENTOUT_87") (pintype "bidirectional"))
      (node (ref "U4") (pin "22") (pinfunction "A12_22") (pintype "passive"))
    )
    (net (code "31") (name "/FSMC-A13") (class "Default")
      (node (ref "U3") (pin "88") (pinfunction "PG3/FSMC_A13/EVENTOUT_88") (pintype "bidirectional"))
      (node (ref "U4") (pin "21") (pinfunction "A13_21") (pintype "passive"))
    )
    (net (code "32") (name "/FSMC-A14") (class "Default")
      (node (ref "U3") (pin "89") (pinfunction "PG4/FSMC_A14/EVENTOUT_89") (pintype "bidirectional"))
      (node (ref "U4") (pin "20") (pinfunction "A14_20") (pintype "passive"))
    )
    (net (code "33") (name "/FSMC-A15") (class "Default")
      (node (ref "U3") (pin "90") (pinfunction "PG5/FSMC_A15/EVENTOUT_90") (pintype "bidirectional"))
      (node (ref "U4") (pin "19") (pinfunction "A15_19") (pintype "passive"))
    )
    (net (code "34") (name "/FSMC-A16") (class "Default")
      (node (ref "U3") (pin "80") (pinfunction "PD11/FSMC_CLE/FSMC_A16/USART3_CTS/EVENTOUT_80") (pintype "bidirectional"))
      (node (ref "U4") (pin "18") (pinfunction "A16_18") (pintype "passive"))
    )
    (net (code "35") (name "/FSMC-A17") (class "Default")
      (node (ref "U3") (pin "81") (pinfunction "PD12/FSMC_ALE/FSMC_A17/TIM4_CH1/USART3_RTS/EVENTOUT_81") (pintype "bidirectional"))
      (node (ref "U4") (pin "23") (pinfunction "A17_23") (pintype "passive"))
    )
    (net (code "36") (name "/FSMC-A18") (class "Default")
      (node (ref "U3") (pin "82") (pinfunction "PD13/FSMC_A18/TIM4_CH2/EVENTOUT_82") (pintype "bidirectional"))
      (node (ref "U4") (pin "28") (pinfunction "A18_28") (pintype "passive"))
    )
    (net (code "37") (name "/FSMC-D0") (class "Default")
      (node (ref "U3") (pin "85") (pinfunction "PD14/FSMC_D0/TIM4_CH3/EVENTOUT/EVENTOUT_85") (pintype "bidirectional"))
      (node (ref "U4") (pin "7") (pinfunction "I/O0_7") (pintype "passive"))
    )
    (net (code "38") (name "/FSMC-D1") (class "Default")
      (node (ref "U3") (pin "86") (pinfunction "PD15/FSMC_D1/TIM4_CH4/EVENTOUT_86") (pintype "bidirectional"))
      (node (ref "U4") (pin "8") (pinfunction "I/O1_8") (pintype "passive"))
    )
    (net (code "39") (name "/FSMC-D2") (class "Default")
      (node (ref "U3") (pin "114") (pinfunction "PD0/FSMC_D2/CAN1_RX/EVENTOUT_114") (pintype "bidirectional"))
      (node (ref "U4") (pin "9") (pinfunction "I/O2_9") (pintype "passive"))
    )
    (net (code "40") (name "/FSMC-D3") (class "Default")
      (node (ref "U3") (pin "115") (pinfunction "PD1/FSMC_D3/CAN1_TX/EVENTOUT_115") (pintype "bidirectional"))
      (node (ref "U4") (pin "10") (pinfunction "I/O3_10") (pintype "passive"))
    )
    (net (code "41") (name "/FSMC-D4") (class "Default")
      (node (ref "U3") (pin "58") (pinfunction "PE7/FSMC_D4/TIM1_ETR/EVENTOUT_58") (pintype "bidirectional"))
      (node (ref "U4") (pin "13") (pinfunction "I/O4_13") (pintype "passive"))
    )
    (net (code "42") (name "/FSMC-D5") (class "Default")
      (node (ref "U3") (pin "59") (pinfunction "PE8/FSMC_D5/TIM1_CH1N/EVENTOUT_59") (pintype "bidirectional"))
      (node (ref "U4") (pin "14") (pinfunction "I/O5_14") (pintype "passive"))
    )
    (net (code "43") (name "/FSMC-D6") (class "Default")
      (node (ref "U3") (pin "60") (pinfunction "PE9/FSMC_D6/TIM1_CH1/EVENTOUT_60") (pintype "bidirectional"))
      (node (ref "U4") (pin "15") (pinfunction "I/O6_15") (pintype "passive"))
    )
    (net (code "44") (name "/FSMC-D7") (class "Default")
      (node (ref "U3") (pin "63") (pinfunction "PE10/FSMC_D7/TIM1_CH2N/EVENTOUT_63") (pintype "bidirectional"))
      (node (ref "U4") (pin "16") (pinfunction "I/O7_16") (pintype "passive"))
    )
    (net (code "45") (name "/FSMC-D8") (class "Default")
      (node (ref "U3") (pin "64") (pinfunction "PE11/FSMC_D8/TIM1_CH2/EVENTOUT_64") (pintype "bidirectional"))
      (node (ref "U4") (pin "29") (pinfunction "I/O8_29") (pintype "passive"))
    )
    (net (code "46") (name "/FSMC-D9") (class "Default")
      (node (ref "U3") (pin "65") (pinfunction "PE12/FSMC_D9/TIM1_CH3N/EVENTOUT_65") (pintype "bidirectional"))
      (node (ref "U4") (pin "30") (pinfunction "I/O9_30") (pintype "passive"))
    )
    (net (code "47") (name "/FSMC-D10") (class "Default")
      (node (ref "U3") (pin "66") (pinfunction "PE13/FSMC_D10/TIM1_CH3/EVENTOUT_66") (pintype "bidirectional"))
      (node (ref "U4") (pin "31") (pinfunction "I/O10_31") (pintype "passive"))
    )
    (net (code "48") (name "/FSMC-D11") (class "Default")
      (node (ref "U3") (pin "67") (pinfunction "PE14/FSMC_D11/TIM1_CH4/EVENTOUT_67") (pintype "bidirectional"))
      (node (ref "U4") (pin "32") (pinfunction "I/O11_32") (pintype "passive"))
    )
    (net (code "49") (name "/FSMC-D12") (class "Default")
      (node (ref "U3") (pin "68") (pinfunction "PE15/FSMC_D12/TIM1_BKIN/EVENTOUT_68") (pintype "bidirectional"))
      (node (ref "U4") (pin "35") (pinfunction "I/O12_35") (pintype "passive"))
    )
    (net (code "50") (name "/FSMC-D13") (class "Default")
      (node (ref "U3") (pin "77") (pinfunction "PD8/FSMC_D13/USART3_TX/EVENTOUT_77") (pintype "bidirectional"))
      (node (ref "U4") (pin "36") (pinfunction "I/O13_36") (pintype "passive"))
    )
    (net (code "51") (name "/FSMC-D14") (class "Default")
      (node (ref "U3") (pin "78") (pinfunction "PD9/FSMC_D14/USART3_RX/EVENTOUT_78") (pintype "bidirectional"))
      (node (ref "U4") (pin "37") (pinfunction "I/O14_37") (pintype "passive"))
    )
    (net (code "52") (name "/FSMC-D15") (class "Default")
      (node (ref "U3") (pin "79") (pinfunction "PD10/FSMC_D15/USART3_CK/EVENTOUT_79") (pintype "bidirectional"))
      (node (ref "U4") (pin "38") (pinfunction "I/O15_38") (pintype "passive"))
    )
    (net (code "53") (name "/FSMC-NBL0") (class "Default")
      (node (ref "U3") (pin "141") (pinfunction "PE0/TIM4_ETR/FSMC_NBL0/DCMI_D2/EVENTOUT_141") (pintype "bidirectional"))
      (node (ref "U4") (pin "39") (pinfunction "~{LB}_39") (pintype "passive"))
    )
    (net (code "54") (name "/FSMC-NBL1") (class "Default")
      (node (ref "U3") (pin "142") (pinfunction "PE1/FSMC_NBL1/DCMI_D3/EVENTOUT_142") (pintype "bidirectional"))
      (node (ref "U4") (pin "40") (pinfunction "~{UB}_40") (pintype "passive"))
    )
    (net (code "55") (name "/FSMC-NE3") (class "Default")
      (node (ref "U3") (pin "125") (pinfunction "PG10/FSMC_NCE4_1/FSMC_NE3/EVENTOUT_125") (pintype "bidirectional"))
      (node (ref "U4") (pin "6") (pinfunction "~{CS1}_6") (pintype "passive"))
    )
    (net (code "56") (name "/FSMC-NOE") (class "Default")
      (node (ref "U3") (pin "118") (pinfunction "PD4/FSMC_NOE/USART2_RTS/EVENTOUT_118") (pintype "bidirectional"))
      (node (ref "U4") (pin "41") (pinfunction "~{O}E_41") (pintype "passive"))
    )
    (net (code "57") (name "/FSMC-NWE") (class "Default")
      (node (ref "U3") (pin "119") (pinfunction "PD5/FSMC_NWE/USART2_TX/EVENTOUT_119") (pintype "bidirectional"))
      (node (ref "U4") (pin "17") (pinfunction "~{WE}_17") (pintype "passive"))
    )
    (net (code "58") (name "/MDC") (class "Default")
      (node (ref "U3") (pin "27") (pinfunction "PC1/ETH_MDC/EVENTOUT/ADC123_IN11_27") (pintype "bidirectional"))
      (node (ref "U9") (pin "13") (pinfunction "MDC_13") (pintype "passive"))
    )
    (net (code "59") (name "/MDIO") (class "Default")
      (node (ref "U3") (pin "36") (pinfunction "PA2/USART2_TX/TIM5_CH3/TIM9_CH1/TIM2_CH3/ETH_MDIO/EVENTOUT/ADC123_IN2_36") (pintype "bidirectional"))
      (node (ref "U9") (pin "12") (pinfunction "MDIO_12") (pintype "passive"))
    )
    (net (code "60") (name "/MISO") (class "Default")
      (node (ref "P5") (pin "15") (pinfunction "15_15") (pintype "passive"))
      (node (ref "U3") (pin "112") (pinfunction "PC11/UART4_RX/SPI3_MISO/SDIO_D3/DCMI_D4/USART3_RX/I2S3ext_SD/EVENTOUT_112") (pintype "bidirectional"))
    )
    (net (code "61") (name "/MOSI") (class "Default")
      (node (ref "P5") (pin "16") (pinfunction "16_16") (pintype "passive"))
      (node (ref "U3") (pin "113") (pinfunction "PC12/UART5_TX/SDIO_CK/DCMI_D9/SPI3_MOSI/I2S3_SD/USART3_CK/EVENTOUT_113") (pintype "bidirectional"))
    )
    (net (code "62") (name "/NRST") (class "Default")
      (node (ref "C15") (pin "2") (pinfunction "2_2") (pintype "passive"))
      (node (ref "P4") (pin "5") (pinfunction "5_5") (pintype "passive"))
      (node (ref "U3") (pin "25") (pinfunction "NRST_25") (pintype "bidirectional"))
    )
    (net (code "63") (name "/REFCLKO") (class "Default")
      (node (ref "U3") (pin "35") (pinfunction "PA1/USART2_RTS/UART4_RX/ETH_RMII_REF_CLK/ETH_MII_RX_CLK/TIM5_CH2/TIM2_CH2/EVENTOUT/ADC123_IN1_35") (pintype "bidirectional"))
      (node (ref "U9") (pin "14") (pinfunction "nINT/REFCLKO_14") (pintype "passive"))
    )
    (net (code "64") (name "/RS232-RXD") (class "Default")
      (node (ref "U3") (pin "97") (pinfunction "PC7/I2S3_MCK/TIM8_CH2/SDIO_D7/USART6_RX/DCMI_D1/TIM3_CH2/EVENTOUT_97") (pintype "bidirectional"))
      (node (ref "U5") (pin "9") (pinfunction "R2OUT_9") (pintype "passive"))
    )
    (net (code "65") (name "/RS232-TXD") (class "Default")
      (node (ref "U3") (pin "96") (pinfunction "PC6/I2S2_MCK/TIM8_CH1/SDIO_D6/USART6_TX/DCMI_D0/TIM3_CH1/EVENTOUT_96") (pintype "bidirectional"))
      (node (ref "U5") (pin "10") (pinfunction "T2IN_10") (pintype "passive"))
    )
    (net (code "66") (name "/RS{slash}AO") (class "Default")
      (node (ref "P5") (pin "11") (pinfunction "11_11") (pintype "passive"))
      (node (ref "U3") (pin "101") (pinfunction "PA9/USART1_TX/TIM1_CH2/I2C3_SMBA/DCMI_D0/EVENTOUT/OTG_FS_VBUS_101") (pintype "bidirectional"))
    )
    (net (code "67") (name "/RXD") (class "Default")
      (node (ref "D9") (pin "2") (pinfunction "K_2") (pintype "passive"))
      (node (ref "P7") (pin "2") (pinfunction "2_2") (pintype "passive"))
      (node (ref "U5") (pin "8") (pinfunction "R2IN_8") (pintype "passive"))
    )
    (net (code "68") (name "/RXD0") (class "Default")
      (node (ref "U3") (pin "44") (pinfunction "PC4/ETH_RMII_RX_D0/ETH_MII_RX_D0/EVENTOUT/ADC12_IN14_44") (pintype "bidirectional"))
      (node (ref "U9") (pin "8") (pinfunction "RXD0/~{MODE0}_8") (pintype "passive"))
    )
    (net (code "69") (name "/RXD1") (class "Default")
      (node (ref "U3") (pin "45") (pinfunction "PC5/ETH_RMII_RX_D1/ETH_MII_RX_D1/EVENTOUT/ADC12_IN15_45") (pintype "bidirectional"))
      (node (ref "U9") (pin "7") (pinfunction "RXD1/~{MODE1}_7") (pintype "passive"))
    )
    (net (code "70") (name "/SCK") (class "Default")
      (node (ref "P5") (pin "14") (pinfunction "14_14") (pintype "passive"))
      (node (ref "U3") (pin "111") (pinfunction "PC10/SPI3_SCK/I2S3_CK/UART4_TX/SDIO_D2/DCMI_D8/USART3_TX/EVENTOUT_111") (pintype "bidirectional"))
    )
    (net (code "71") (name "/SPI-CLK") (class "Default")
      (node (ref "U3") (pin "133") (pinfunction "PB3(JTDO/TRACESWO)/JTDO/TRACESWO/SPI3_SCK/I2S3_CK/TIM2_CH2/SPI1_SCK/EVENTOUT_133") (pintype "bidirectional"))
      (node (ref "U6") (pin "6") (pinfunction "CLK_6") (pintype "passive"))
    )
    (net (code "72") (name "/SPI-DI") (class "Default")
      (node (ref "U3") (pin "134") (pinfunction "PB4(NJTRST)/NJTRST/SPI3_MISO/TIM3_CH1/SPI1_MISO/I2S3ext_SD/EVENTOUT_134") (pintype "bidirectional"))
      (node (ref "U6") (pin "2") (pinfunction "DO(IO1)_2") (pintype "passive"))
    )
    (net (code "73") (name "/SPI-DO") (class "Default")
      (node (ref "U3") (pin "135") (pinfunction "PB5/I2C1_SMBA/CAN2_RX/OTG_HS_ULPI_D7/ETH_PPS_OUT/TIM3_CH2/SPI1_MOSI/SPI3_MOSI/DCMI_D10/I2S3_SD/EVENTOUT_135") (pintype "bidirectional"))
      (node (ref "U6") (pin "5") (pinfunction "DI(IO0)_5") (pintype "passive"))
    )
    (net (code "74") (name "/SPI-~{CS}") (class "Default")
      (node (ref "U3") (pin "136") (pinfunction "PB6/I2C1_SCL/TIM4_CH1/CAN2_TX/DCMI_D5/USART1_TX/EVENTOUT_136") (pintype "bidirectional"))
      (node (ref "U6") (pin "1") (pinfunction "~{CS}_1") (pintype "passive"))
    )
    (net (code "75") (name "/SPI-~{HOLD}") (class "Default")
      (node (ref "U3") (pin "132") (pinfunction "PG15/USART6_CTS/DCMI_D13/EVENTOUT_132") (pintype "bidirectional"))
      (node (ref "U6") (pin "7") (pinfunction "~{HOLD}_or_~{RESET}(IO3)_7") (pintype "passive"))
    )
    (net (code "76") (name "/SPI-~{WP}") (class "Default")
      (node (ref "U3") (pin "137") (pinfunction "PB7/I2C1_SDA/FSMC_NL/DCMI_VSYNC/USART1_RX/TIM4_CH2/EVENTOUT_137") (pintype "bidirectional"))
      (node (ref "U6") (pin "3") (pinfunction "~{WP}(IO2)_3") (pintype "passive"))
    )
    (net (code "77") (name "/SWCLK") (class "Default")
      (node (ref "P4") (pin "2") (pinfunction "2_2") (pintype "passive"))
      (node (ref "U3") (pin "109") (pinfunction "PA14(JTCK-SWCLK)/JTCK-SWCLK/EVENTOUT_109") (pintype "bidirectional"))
    )
    (net (code "78") (name "/SWDIO") (class "Default")
      (node (ref "P4") (pin "4") (pinfunction "4_4") (pintype "passive"))
      (node (ref "U3") (pin "105") (pinfunction "PA13(JTMS-SWDIO)/JTMS-SWDIO/EVENTOUT_105") (pintype "bidirectional"))
    )
    (net (code "79") (name "/TXD") (class "Default")
      (node (ref "D8") (pin "2") (pinfunction "K_2") (pintype "passive"))
      (node (ref "P7") (pin "1") (pinfunction "1_1") (pintype "passive"))
      (node (ref "U5") (pin "7") (pinfunction "T2OUT_7") (pintype "passive"))
    )
    (net (code "80") (name "/TXD0") (class "Default")
      (node (ref "U3") (pin "128") (pinfunction "PG13/FSMC_A24/USART6_CTS/ETH_MII_TXD0/ETH_RMII_TXD0/EVENTOUT_128") (pintype "bidirectional"))
      (node (ref "U9") (pin "17") (pinfunction "TXD0_17") (pintype "passive"))
    )
    (net (code "81") (name "/TXD1") (class "Default")
      (node (ref "U3") (pin "129") (pinfunction "PG14/FSMC_A25/USART6_TX/ETH_MII_TXD1/ETH_RMII_TXD1/EVENTOUT_129") (pintype "bidirectional"))
      (node (ref "U9") (pin "18") (pinfunction "TXD1_18") (pintype "passive"))
    )
    (net (code "82") (name "/TXEN") (class "Default")
      (node (ref "U3") (pin "126") (pinfunction "PG11/FSMC_NCE4_2/ETH_MII_TX_EN/ETH_RMII_TX_EN/EVENTOUT_126") (pintype "bidirectional"))
      (node (ref "U9") (pin "16") (pinfunction "TXEN_16") (pintype "passive"))
    )
    (net (code "83") (name "/VBAT") (class "Default")
      (node (ref "B1") (pin "1") (pinfunction "+_1") (pintype "passive"))
      (node (ref "C12") (pin "2") (pinfunction "2_2") (pintype "passive"))
      (node (ref "D5") (pin "2") (pinfunction "K_2") (pintype "passive"))
      (node (ref "U3") (pin "6") (pinfunction "VBAT_6") (pintype "power_in"))
    )
    (net (code "84") (name "/屏幕CS") (class "Default")
      (node (ref "P5") (pin "17") (pinfunction "17_17") (pintype "passive"))
      (node (ref "U3") (pin "116") (pinfunction "PD2/TIM3_ETR/UART5_RX/SDIO_CMD/DCMI_D11/EVENTOUT_116") (pintype "bidirectional"))
    )
    (net (code "85") (name "/按键-上") (class "Default")
      (node (ref "P5") (pin "8") (pinfunction "8_8") (pintype "passive"))
      (node (ref "U3") (pin "98") (pinfunction "PC8/TIM8_CH3/SDIO_D0/TIM3_CH3/USART6_CK/DCMI_D2/EVENTOUT_98") (pintype "bidirectional"))
    )
    (net (code "86") (name "/按键-下") (class "Default")
      (node (ref "P5") (pin "9") (pinfunction "9_9") (pintype "passive"))
      (node (ref "U3") (pin "99") (pinfunction "PC9/I2S_CKIN/MCO2/TIM8_CH4/SDIO_D1//I2C3_SDA/DCMI_D3/TIM3_CH4/EVENTOUT_99") (pintype "bidirectional"))
    )
    (net (code "87") (name "/按键-中") (class "Default")
      (node (ref "P5") (pin "7") (pinfunction "7_7") (pintype "passive"))
      (node (ref "U3") (pin "93") (pinfunction "PG8/USART6_RTS/ETH_PPS_OUT/EVENTOUT_93") (pintype "bidirectional"))
    )
    (net (code "88") (name "/按键-右") (class "Default")
      (node (ref "P5") (pin "10") (pinfunction "10_10") (pintype "passive"))
      (node (ref "U3") (pin "100") (pinfunction "PA8/MCO1/USART1_CK/TIM1_CH1/I2C3_SCL/OTG_FS_SOF/EVENTOUT_100") (pintype "bidirectional"))
    )
    (net (code "89") (name "/按键-左") (class "Default")
      (node (ref "P5") (pin "6") (pinfunction "6_6") (pintype "passive"))
      (node (ref "U3") (pin "92") (pinfunction "PG7/FSMC_INT3/USART6_CK/EVENTOUT_92") (pintype "bidirectional"))
    )
    (net (code "90") (name "/背光使能") (class "Default")
      (node (ref "P5") (pin "18") (pinfunction "18_18") (pintype "passive"))
      (node (ref "U3") (pin "117") (pinfunction "PD3/FSMC_CLK/USART2_CTS/EVENTOUT_117") (pintype "bidirectional"))
    )
    (net (code "91") (name "/触摸CS") (class "Default")
      (node (ref "P5") (pin "13") (pinfunction "13_13") (pintype "passive"))
      (node (ref "U3") (pin "110") (pinfunction "PA15(JTDI)/JTDI/SPI3_NSS/I2S3_WS/TIM2_CH1_ETR/SPI1_NSS/EVENTOUT_110") (pintype "bidirectional"))
    )
    (net (code "92") (name "/触摸中断") (class "Default")
      (node (ref "P5") (pin "12") (pinfunction "12_12") (pintype "passive"))
      (node (ref "U3") (pin "102") (pinfunction "PA10/USART1_RX/TIM1_CH3/OTG_FS_ID/DCMI_D1/EVENTOUT_102") (pintype "bidirectional"))
    )
    (net (code "93") (name "3.3V") (class "Default")
      (node (ref "C10") (pin "2") (pinfunction "2_2") (pintype "passive"))
      (node (ref "C11") (pin "2") (pinfunction "2_2") (pintype "passive"))
      (node (ref "C21") (pin "2") (pinfunction "2_2") (pintype "passive"))
      (node (ref "C22") (pin "2") (pinfunction "2_2") (pintype "passive"))
      (node (ref "C25") (pin "2") (pinfunction "2_2") (pintype "passive"))
      (node (ref "C26") (pin "2") (pinfunction "2_2") (pintype "passive"))
      (node (ref "C3") (pin "1") (pinfunction "1_1") (pintype "passive"))
      (node (ref "C36") (pin "2") (pinfunction "2_2") (pintype "passive"))
      (node (ref "C37") (pin "2") (pinfunction "2_2") (pintype "passive"))
      (node (ref "C38") (pin "1") (pinfunction "1_1") (pintype "passive"))
      (node (ref "C39") (pin "2") (pinfunction "2_2") (pintype "passive"))
      (node (ref "C40") (pin "2") (pinfunction "2_2") (pintype "passive"))
      (node (ref "C41") (pin "2") (pinfunction "2_2") (pintype "passive"))
      (node (ref "C42") (pin "2") (pinfunction "2_2") (pintype "passive"))
      (node (ref "C43") (pin "2") (pinfunction "2_2") (pintype "passive"))
      (node (ref "D10") (pin "1") (pinfunction "A_1") (pintype "passive"))
      (node (ref "I1") (pin "2") (pinfunction "2_2") (pintype "passive"))
      (node (ref "L1") (pin "2") (pinfunction "2_2") (pintype "passive"))
      (node (ref "P4") (pin "1") (pinfunction "1_1") (pintype "passive"))
      (node (ref "P5") (pin "2") (pinfunction "2_2") (pintype "passive"))
      (node (ref "P5") (pin "3") (pinfunction "3_3") (pintype "passive"))
      (node (ref "R1") (pin "2") (pinfunction "2_2") (pintype "passive"))
      (node (ref "R16") (pin "2") (pinfunction "2_2") (pintype "passive"))
      (node (ref "R3") (pin "2") (pinfunction "2_2") (pintype "passive"))
      (node (ref "S2") (pin "3") (pinfunction "3_3") (pintype "passive"))
      (node (ref "S2") (pin "4") (pinfunction "4_4") (pintype "passive"))
      (node (ref "U10") (pin "5") (pinfunction "Vio_5") (pintype "passive"))
      (node (ref "U3") (pin "108") (pinfunction "VDD_108") (pintype "power_in"))
      (node (ref "U3") (pin "121") (pinfunction "VDD_121") (pintype "power_in"))
      (node (ref "U3") (pin "131") (pinfunction "VDD_131") (pintype "power_in"))
      (node (ref "U3") (pin "143") (pinfunction "PDR_ON_143") (pintype "input"))
      (node (ref "U3") (pin "144") (pinfunction "VDD_144") (pintype "power_in"))
      (node (ref "U3") (pin "17") (pinfunction "VDD_17") (pintype "power_in"))
      (node (ref "U3") (pin "30") (pinfunction "VDD_30") (pintype "power_in"))
      (node (ref "U3") (pin "32") (pinfunction "VREF+_32") (pintype "power_in"))
      (node (ref "U3") (pin "33") (pinfunction "VDDA_33") (pintype "power_in"))
      (node (ref "U3") (pin "39") (pinfunction "VDD_39") (pintype "power_in"))
      (node (ref "U3") (pin "52") (pinfunction "VDD_52") (pintype "power_in"))
      (node (ref "U3") (pin "62") (pinfunction "VDD_62") (pintype "power_in"))
      (node (ref "U3") (pin "72") (pinfunction "VDD_72") (pintype "power_in"))
      (node (ref "U3") (pin "84") (pinfunction "VDD_84") (pintype "power_in"))
      (node (ref "U3") (pin "95") (pinfunction "VDD_95") (pintype "power_in"))
      (node (ref "U4") (pin "11") (pinfunction "VDD_11") (pintype "passive"))
      (node (ref "U4") (pin "33") (pinfunction "VDD_33") (pintype "passive"))
      (node (ref "U5") (pin "16") (pinfunction "VCC_16") (pintype "passive"))
      (node (ref "U6") (pin "8") (pinfunction "VCC_8") (pintype "passive"))
      (node (ref "U7") (pin "8") (pinfunction "VCC_8") (pintype "passive"))
      (node (ref "U8") (pin "5") (pinfunction "Vio_5") (pintype "passive"))
      (node (ref "U9") (pin "9") (pinfunction "VDDIO_9") (pintype "passive"))
    )
    (net (code "94") (name "5V") (class "Default")
      (node (ref "C2") (pin "1") (pinfunction "1_1") (pintype "passive"))
      (node (ref "C5") (pin "2") (pinfunction "2_2") (pintype "passive"))
      (node (ref "C6") (pin "2") (pinfunction "2_2") (pintype "passive"))
      (node (ref "C7") (pin "2") (pinfunction "2_2") (pintype "passive"))
      (node (ref "C8") (pin "2") (pinfunction "2_2") (pintype "passive"))
      (node (ref "C9") (pin "2") (pinfunction "2_2") (pintype "passive"))
      (node (ref "D3") (pin "2") (pinfunction "K_2") (pintype "passive"))
      (node (ref "D6") (pin "2") (pinfunction "K_2") (pintype "passive"))
      (node (ref "L2") (pin "2") (pinfunction "2_2") (pintype "passive"))
      (node (ref "P5") (pin "1") (pinfunction "1_1") (pintype "passive"))
      (node (ref "U1") (pin "3") (pinfunction "FEEDBACK_3") (pintype "passive"))
      (node (ref "U10") (pin "3") (pinfunction "VCC_3") (pintype "passive"))
      (node (ref "U2") (pin "1") (pinfunction "EN_1") (pintype "passive"))
      (node (ref "U2") (pin "4") (pinfunction "VIN_4") (pintype "passive"))
      (node (ref "U8") (pin "3") (pinfunction "VCC_3") (pintype "passive"))
    )
    (net (code "95") (name "GND") (class "Default")
      (node (ref "B1") (pin "2") (pinfunction "-_2") (pintype "passive"))
      (node (ref "C1") (pin "2") (pinfunction "2_2") (pintype "passive"))
      (node (ref "C11") (pin "1") (pinfunction "1_1") (pintype "passive"))
      (node (ref "C12") (pin "1") (pinfunction "1_1") (pintype "passive"))
      (node (ref "C13") (pin "1") (pinfunction "1_1") (pintype "passive"))
      (node (ref "C14") (pin "1") (pinfunction "1_1") (pintype "passive"))
      (node (ref "C15") (pin "1") (pinfunction "1_1") (pintype "passive"))
      (node (ref "C16") (pin "2") (pinfunction "2_2") (pintype "passive"))
      (node (ref "C17") (pin "2") (pinfunction "2_2") (pintype "passive"))
      (node (ref "C18") (pin "2") (pinfunction "2_2") (pintype "passive"))
      (node (ref "C19") (pin "2") (pinfunction "2_2") (pintype "passive"))
      (node (ref "C2") (pin "2") (pinfunction "2_2") (pintype "passive"))
      (node (ref "C22") (pin "1") (pinfunction "1_1") (pintype "passive"))
      (node (ref "C24") (pin "1") (pinfunction "1_1") (pintype "passive"))
      (node (ref "C25") (pin "1") (pinfunction "1_1") (pintype "passive"))
      (node (ref "C26") (pin "1") (pinfunction "1_1") (pintype "passive"))
      (node (ref "C27") (pin "1") (pinfunction "1_1") (pintype "passive"))
      (node (ref "C28") (pin "1") (pinfunction "1_1") (pintype "passive"))
      (node (ref "C29") (pin "1") (pinfunction "1_1") (pintype "passive"))
      (node (ref "C3") (pin "2") (pinfunction "2_2") (pintype "passive"))
      (node (ref "C31") (pin "2") (pinfunction "2_2") (pintype "passive"))
      (node (ref "C32") (pin "2") (pinfunction "2_2") (pintype "passive"))
      (node (ref "C34") (pin "1") (pinfunction "1_1") (pintype "passive"))
      (node (ref "C35") (pin "1") (pinfunction "1_1") (pintype "passive"))
      (node (ref "C36") (pin "1") (pinfunction "1_1") (pintype "passive"))
      (node (ref "C37") (pin "1") (pinfunction "1_1") (pintype "passive"))
      (node (ref "C38") (pin "2") (pinfunction "2_2") (pintype "passive"))
      (node (ref "C39") (pin "1") (pinfunction "1_1") (pintype "passive"))
      (node (ref "C4") (pin "1") (pinfunction "1_1") (pintype "passive"))
      (node (ref "C40") (pin "1") (pinfunction "1_1") (pintype "passive"))
      (node (ref "C41") (pin "1") (pinfunction "1_1") (pintype "passive"))
      (node (ref "C42") (pin "1") (pinfunction "1_1") (pintype "passive"))
      (node (ref "C43") (pin "1") (pinfunction "1_1") (pintype "passive"))
      (node (ref "C5") (pin "1") (pinfunction "1_1") (pintype "passive"))
      (node (ref "C6") (pin "1") (pinfunction "1_1") (pintype "passive"))
      (node (ref "C7") (pin "1") (pinfunction "1_1") (pintype "passive"))
      (node (ref "C8") (pin "1") (pinfunction "1_1") (pintype "passive"))
      (node (ref "C9") (pin "1") (pinfunction "1_1") (pintype "passive"))
      (node (ref "D11") (pin "1") (pinfunction "A_1") (pintype "passive"))
      (node (ref "D12") (pin "1") (pinfunction "A_1") (pintype "passive"))
      (node (ref "D13") (pin "1") (pinfunction "A_1") (pintype "passive"))
      (node (ref "D14") (pin "1") (pinfunction "A_1") (pintype "passive"))
      (node (ref "D15") (pin "1") (pinfunction "A_1") (pintype "passive"))
      (node (ref "D16") (pin "1") (pinfunction "A_1") (pintype "passive"))
      (node (ref "D2") (pin "1") (pinfunction "A_1") (pintype "passive"))
      (node (ref "D3") (pin "1") (pinfunction "A_1") (pintype "passive"))
      (node (ref "D4") (pin "1") (pinfunction "A_1") (pintype "passive"))
      (node (ref "D7") (pin "3") (pinfunction "A_3") (pintype "passive"))
      (node (ref "D8") (pin "1") (pinfunction "A_1") (pintype "passive"))
      (node (ref "D9") (pin "1") (pinfunction "A_1") (pintype "passive"))
      (node (ref "P1") (pin "2") (pinfunction "2_2") (pintype "passive"))
      (node (ref "P2") (pin "2") (pinfunction "2_2") (pintype "passive"))
      (node (ref "P4") (pin "3") (pinfunction "3_3") (pintype "passive"))
      (node (ref "P5") (pin "19") (pinfunction "19_19") (pintype "passive"))
      (node (ref "P5") (pin "20") (pinfunction "20_20") (pintype "passive"))
      (node (ref "P5") (pin "4") (pinfunction "4_4") (pintype "passive"))
      (node (ref "P5") (pin "5") (pinfunction "5_5") (pintype "passive"))
      (node (ref "P6") (pin "4") (pinfunction "GND_4") (pintype "passive"))
      (node (ref "P7") (pin "3") (pinfunction "3_3") (pintype "passive"))
      (node (ref "R15") (pin "2") (pinfunction "2_2") (pintype "passive"))
      (node (ref "R19") (pin "2") (pinfunction "2_2") (pintype "passive"))
      (node (ref "R2") (pin "1") (pinfunction "1_1") (pintype "passive"))
      (node (ref "R20") (pin "2") (pinfunction "2_2") (pintype "passive"))
      (node (ref "R21") (pin "1") (pinfunction "1_1") (pintype "passive"))
      (node (ref "R22") (pin "1") (pinfunction "1_1") (pintype "passive"))
      (node (ref "R23") (pin "1") (pinfunction "1_1") (pintype "passive"))
      (node (ref "R8") (pin "1") (pinfunction "1_1") (pintype "passive"))
      (node (ref "U1") (pin "4") (pinfunction "ON/OFF_4") (pintype "passive"))
      (node (ref "U1") (pin "5") (pinfunction "GND_5") (pintype "passive"))
      (node (ref "U1") (pin "6") (pinfunction "GND_6") (pintype "passive"))
      (node (ref "U1") (pin "7") (pinfunction "GND_7") (pintype "passive"))
      (node (ref "U1") (pin "8") (pinfunction "GND_8") (pintype "passive"))
      (node (ref "U10") (pin "2") (pinfunction "GND_2") (pintype "passive"))
      (node (ref "U10") (pin "8") (pinfunction "S_8") (pintype "passive"))
      (node (ref "U2") (pin "2") (pinfunction "GND_2") (pintype "passive"))
      (node (ref "U3") (pin "107") (pinfunction "VSS_107") (pintype "power_in"))
      (node (ref "U3") (pin "120") (pinfunction "VSS_120") (pintype "power_in"))
      (node (ref "U3") (pin "130") (pinfunction "VSS_130") (pintype "power_in"))
      (node (ref "U3") (pin "16") (pinfunction "VSS_16") (pintype "power_in"))
      (node (ref "U3") (pin "31") (pinfunction "VSSA_31") (pintype "power_in"))
      (node (ref "U3") (pin "38") (pinfunction "VSS_38") (pintype "power_in"))
      (node (ref "U3") (pin "51") (pinfunction "VSS_51") (pintype "power_in"))
      (node (ref "U3") (pin "61") (pinfunction "VSS_61") (pintype "power_in"))
      (node (ref "U3") (pin "83") (pinfunction "VSS_83") (pintype "power_in"))
      (node (ref "U3") (pin "94") (pinfunction "VSS_94") (pintype "power_in"))
      (node (ref "U4") (pin "12") (pinfunction "GND_12") (pintype "passive"))
      (node (ref "U4") (pin "34") (pinfunction "GND_34") (pintype "passive"))
      (node (ref "U5") (pin "15") (pinfunction "GND_15") (pintype "passive"))
      (node (ref "U6") (pin "4") (pinfunction "GND_4") (pintype "passive"))
      (node (ref "U7") (pin "5") (pinfunction "GND_5") (pintype "passive"))
      (node (ref "U8") (pin "2") (pinfunction "GND_2") (pintype "passive"))
      (node (ref "U8") (pin "8") (pinfunction "S_8") (pintype "passive"))
      (node (ref "U9") (pin "25") (pinfunction "GND_25") (pintype "passive"))
    )
    (net (code "96") (name "Net-(C33-Pad1)") (class "Default")
      (node (ref "C33") (pin "1") (pinfunction "1_1") (pintype "passive"))
      (node (ref "R17") (pin "1") (pinfunction "1_1") (pintype "passive"))
      (node (ref "R18") (pin "2") (pinfunction "2_2") (pintype "passive"))
    )
    (net (code "97") (name "Net-(D1-A)") (class "Default")
      (node (ref "D1") (pin "1") (pinfunction "A_1") (pintype "passive"))
      (node (ref "F1") (pin "2") (pinfunction "2_2") (pintype "passive"))
    )
    (net (code "98") (name "Net-(D1-K)") (class "Default")
      (node (ref "C1") (pin "1") (pinfunction "1_1") (pintype "passive"))
      (node (ref "C4") (pin "2") (pinfunction "2_2") (pintype "passive"))
      (node (ref "D1") (pin "2") (pinfunction "K_2") (pintype "passive"))
      (node (ref "D2") (pin "2") (pinfunction "K_2") (pintype "passive"))
      (node (ref "U1") (pin "1") (pinfunction "VIN_1") (pintype "passive"))
    )
    (net (code "99") (name "Net-(D4-K)") (class "Default")
      (node (ref "D4") (pin "2") (pinfunction "K_2") (pintype "passive"))
      (node (ref "L2") (pin "1") (pinfunction "1_1") (pintype "passive"))
      (node (ref "U1") (pin "2") (pinfunction "OUTPUT_2") (pintype "passive"))
    )
    (net (code "100") (name "Net-(D5-A)") (class "Default")
      (node (ref "D5") (pin "1") (pinfunction "A_1") (pintype "passive"))
      (node (ref "R3") (pin "1") (pinfunction "1_1") (pintype "passive"))
    )
    (net (code "101") (name "Net-(D6-A)") (class "Default")
      (node (ref "D6") (pin "1") (pinfunction "A_1") (pintype "passive"))
      (node (ref "P6") (pin "1") (pinfunction "5V_1") (pintype "passive"))
    )
    (net (code "102") (name "Net-(D10-K)") (class "Default")
      (node (ref "D10") (pin "2") (pinfunction "K_2") (pintype "passive"))
      (node (ref "R4") (pin "1") (pinfunction "1_1") (pintype "passive"))
    )
    (net (code "103") (name "Net-(F1-Pad1)") (class "Default")
      (node (ref "F1") (pin "1") (pinfunction "1_1") (pintype "passive"))
      (node (ref "P1") (pin "1") (pinfunction "1_1") (pintype "passive"))
      (node (ref "P2") (pin "1") (pinfunction "1_1") (pintype "passive"))
    )
    (net (code "104") (name "Net-(P6-D+)") (class "Default")
      (node (ref "D7") (pin "1") (pinfunction "K_1") (pintype "passive"))
      (node (ref "P6") (pin "3") (pinfunction "D+_3") (pintype "passive"))
      (node (ref "U3") (pin "104") (pinfunction "PA12/USART1_RTS/CAN1_TX/TIM1_ETR/OTG_FS_DP/EVENTOUT_104") (pintype "bidirectional"))
    )
    (net (code "105") (name "Net-(P6-D-)") (class "Default")
      (node (ref "D7") (pin "2") (pinfunction "K_2") (pintype "passive"))
      (node (ref "P6") (pin "2") (pinfunction "D-_2") (pintype "passive"))
      (node (ref "U3") (pin "103") (pinfunction "PA11/USART1_CTS/CAN1_RX/TIM1_CH4/OTG_FS_DM/EVENTOUT_103") (pintype "bidirectional"))
    )
    (net (code "106") (name "Net-(P14-RD+)") (class "Default")
      (node (ref "D17") (pin "3") (pinfunction "3_3") (pintype "passive"))
      (node (ref "D17") (pin "6") (pinfunction "6_6") (pintype "passive"))
      (node (ref "P14") (pin "3") (pinfunction "RD+_3") (pintype "passive"))
      (node (ref "T1") (pin "11") (pinfunction "11_11") (pintype "passive"))
    )
    (net (code "107") (name "Net-(P14-RD-)") (class "Default")
      (node (ref "D17") (pin "4") (pinfunction "4_4") (pintype "passive"))
      (node (ref "D17") (pin "5") (pinfunction "5_5") (pintype "passive"))
      (node (ref "P14") (pin "6") (pinfunction "RD-_6") (pintype "passive"))
      (node (ref "T1") (pin "9") (pinfunction "9_9") (pintype "passive"))
    )
    (net (code "108") (name "Net-(P14-TD+)") (class "Default")
      (node (ref "D17") (pin "1") (pinfunction "1_1") (pintype "passive"))
      (node (ref "D17") (pin "8") (pinfunction "8_8") (pintype "passive"))
      (node (ref "P14") (pin "1") (pinfunction "TD+_1") (pintype "passive"))
      (node (ref "T1") (pin "16") (pinfunction "16_16") (pintype "passive"))
    )
    (net (code "109") (name "Net-(P14-TD-)") (class "Default")
      (node (ref "D17") (pin "2") (pinfunction "2_2") (pintype "passive"))
      (node (ref "D17") (pin "7") (pinfunction "7_7") (pintype "passive"))
      (node (ref "P14") (pin "2") (pinfunction "TD-_2") (pintype "passive"))
      (node (ref "T1") (pin "14") (pinfunction "14_14") (pintype "passive"))
    )
    (net (code "110") (name "Net-(P14-绿LED+)") (class "Default")
      (node (ref "P14") (pin "11") (pinfunction "绿LED+_11") (pintype "passive"))
      (node (ref "U9") (pin "3") (pinfunction "LED1/~{REGOFF}_3") (pintype "passive"))
    )
    (net (code "111") (name "Net-(P14-绿LED-)") (class "Default")
      (node (ref "P14") (pin "12") (pinfunction "绿LED-_12") (pintype "passive"))
      (node (ref "R21") (pin "2") (pinfunction "2_2") (pintype "passive"))
    )
    (net (code "112") (name "Net-(P14-黄LED+)") (class "Default")
      (node (ref "P14") (pin "9") (pinfunction "黄LED+_9") (pintype "passive"))
      (node (ref "U9") (pin "2") (pinfunction "LED2/~{nNTSEL}_2") (pintype "passive"))
    )
    (net (code "113") (name "Net-(P14-黄LED-)") (class "Default")
      (node (ref "P14") (pin "10") (pinfunction "黄LED-_10") (pintype "passive"))
      (node (ref "R20") (pin "1") (pinfunction "1_1") (pintype "passive"))
    )
    (net (code "114") (name "Net-(R6-Pad2)") (class "Default")
      (node (ref "R6") (pin "2") (pinfunction "2_2") (pintype "passive"))
      (node (ref "S1") (pin "6") (pinfunction "6_6") (pintype "passive"))
    )
    (net (code "115") (name "Net-(R9-Pad2)") (class "Default")
      (node (ref "R9") (pin "2") (pinfunction "2_2") (pintype "passive"))
      (node (ref "S1") (pin "5") (pinfunction "5_5") (pintype "passive"))
    )
    (net (code "116") (name "Net-(R10-Pad2)") (class "Default")
      (node (ref "R10") (pin "2") (pinfunction "2_2") (pintype "passive"))
      (node (ref "S1") (pin "4") (pinfunction "4_4") (pintype "passive"))
    )
    (net (code "117") (name "Net-(R17-Pad2)") (class "Default")
      (node (ref "R17") (pin "2") (pinfunction "2_2") (pintype "passive"))
      (node (ref "T1") (pin "15") (pinfunction "15_15") (pintype "passive"))
    )
    (net (code "118") (name "Net-(R18-Pad1)") (class "Default")
      (node (ref "R18") (pin "1") (pinfunction "1_1") (pintype "passive"))
      (node (ref "T1") (pin "10") (pinfunction "10_10") (pintype "passive"))
    )
    (net (code "119") (name "Net-(U2-SW)") (class "Default")
      (node (ref "L1") (pin "1") (pinfunction "1_1") (pintype "passive"))
      (node (ref "U2") (pin "3") (pinfunction "SW_3") (pintype "passive"))
    )
    (net (code "120") (name "Net-(U2-VOUT{slash}FB)") (class "Default")
      (node (ref "C10") (pin "1") (pinfunction "1_1") (pintype "passive"))
      (node (ref "R1") (pin "1") (pinfunction "1_1") (pintype "passive"))
      (node (ref "R2") (pin "2") (pinfunction "2_2") (pintype "passive"))
      (node (ref "U2") (pin "5") (pinfunction "VOUT/FB_5") (pintype "passive"))
    )
    (net (code "121") (name "Net-(U3-PC14-OSC32_IN(PC14){slash}EVENTOUT{slash}OSC32_IN)") (class "Default")
      (node (ref "C18") (pin "1") (pinfunction "1_1") (pintype "passive"))
      (node (ref "U3") (pin "8") (pinfunction "PC14-OSC32_IN(PC14)/EVENTOUT/OSC32_IN_8") (pintype "bidirectional"))
      (node (ref "Y2") (pin "2") (pinfunction "OSC2_2") (pintype "passive"))
    )
    (net (code "122") (name "Net-(U3-PC15-OSC32_OUT(PC15){slash}EVENTOUT{slash}OSC32_OUT)") (class "Default")
      (node (ref "C19") (pin "1") (pinfunction "1_1") (pintype "passive"))
      (node (ref "U3") (pin "9") (pinfunction "PC15-OSC32_OUT(PC15)/EVENTOUT/OSC32_OUT_9") (pintype "bidirectional"))
      (node (ref "Y2") (pin "1") (pinfunction "OSC1_1") (pintype "passive"))
    )
    (net (code "123") (name "Net-(U3-PH0-OSC_IN(PH0){slash}EVENTOUT{slash}OSC_IN)") (class "Default")
      (node (ref "C16") (pin "1") (pinfunction "1_1") (pintype "passive"))
      (node (ref "U3") (pin "23") (pinfunction "PH0-OSC_IN(PH0)/EVENTOUT/OSC_IN_23") (pintype "bidirectional"))
      (node (ref "Y1") (pin "2") (pinfunction "OSC2_2") (pintype "passive"))
    )
    (net (code "124") (name "Net-(U3-PH1-OSC_OUT(PH1){slash}EVENTOUT{slash}OSC_OUT)") (class "Default")
      (node (ref "C17") (pin "1") (pinfunction "1_1") (pintype "passive"))
      (node (ref "U3") (pin "24") (pinfunction "PH1-OSC_OUT(PH1)/EVENTOUT/OSC_OUT_24") (pintype "bidirectional"))
      (node (ref "Y1") (pin "1") (pinfunction "OSC1_1") (pintype "passive"))
    )
    (net (code "125") (name "Net-(U3-VCAP_1)") (class "Default")
      (node (ref "C13") (pin "2") (pinfunction "2_2") (pintype "passive"))
      (node (ref "U3") (pin "71") (pinfunction "VCAP_1_71") (pintype "power_in"))
    )
    (net (code "126") (name "Net-(U3-VCAP_2)") (class "Default")
      (node (ref "C14") (pin "2") (pinfunction "2_2") (pintype "passive"))
      (node (ref "U3") (pin "106") (pinfunction "VCAP_2_106") (pintype "power_in"))
    )
    (net (code "127") (name "Net-(U5-C1+)") (class "Default")
      (node (ref "C20") (pin "2") (pinfunction "2_2") (pintype "passive"))
      (node (ref "U5") (pin "1") (pinfunction "C1+_1") (pintype "passive"))
    )
    (net (code "128") (name "Net-(U5-C1-)") (class "Default")
      (node (ref "C20") (pin "1") (pinfunction "1_1") (pintype "passive"))
      (node (ref "U5") (pin "3") (pinfunction "C1-_3") (pintype "passive"))
    )
    (net (code "129") (name "Net-(U5-C2+)") (class "Default")
      (node (ref "C23") (pin "2") (pinfunction "2_2") (pintype "passive"))
      (node (ref "U5") (pin "4") (pinfunction "C2+_4") (pintype "passive"))
    )
    (net (code "130") (name "Net-(U5-C2-)") (class "Default")
      (node (ref "C23") (pin "1") (pinfunction "1_1") (pintype "passive"))
      (node (ref "U5") (pin "5") (pinfunction "C2-_5") (pintype "passive"))
    )
    (net (code "131") (name "Net-(U5-V+)") (class "Default")
      (node (ref "C21") (pin "1") (pinfunction "1_1") (pintype "passive"))
      (node (ref "U5") (pin "2") (pinfunction "V+_2") (pintype "passive"))
    )
    (net (code "132") (name "Net-(U5-V-)") (class "Default")
      (node (ref "C24") (pin "2") (pinfunction "2_2") (pintype "passive"))
      (node (ref "U5") (pin "6") (pinfunction "V-_6") (pintype "passive"))
    )
    (net (code "133") (name "Net-(U7-A)") (class "Default")
      (node (ref "R5") (pin "2") (pinfunction "2_2") (pintype "passive"))
      (node (ref "U7") (pin "6") (pinfunction "A_6") (pintype "passive"))
    )
    (net (code "134") (name "Net-(U7-B)") (class "Default")
      (node (ref "R7") (pin "2") (pinfunction "2_2") (pintype "passive"))
      (node (ref "U7") (pin "7") (pinfunction "B_7") (pintype "passive"))
    )
    (net (code "135") (name "Net-(U9-RBIAS)") (class "Default")
      (node (ref "R19") (pin "1") (pinfunction "1_1") (pintype "passive"))
      (node (ref "U9") (pin "24") (pinfunction "RBIAS_24") (pintype "passive"))
    )
    (net (code "136") (name "Net-(U9-RXER{slash}~{PHYAD0})") (class "Default")
      (node (ref "R15") (pin "1") (pinfunction "1_1") (pintype "passive"))
      (node (ref "U9") (pin "10") (pinfunction "RXER/~{PHYAD0}_10") (pintype "passive"))
    )
    (net (code "137") (name "Net-(U9-RXN)") (class "Default")
      (node (ref "R14") (pin "1") (pinfunction "1_1") (pintype "passive"))
      (node (ref "T1") (pin "8") (pinfunction "8_8") (pintype "passive"))
      (node (ref "U9") (pin "22") (pinfunction "RXN_22") (pintype "passive"))
    )
    (net (code "138") (name "Net-(U9-RXP)") (class "Default")
      (node (ref "R13") (pin "1") (pinfunction "1_1") (pintype "passive"))
      (node (ref "T1") (pin "6") (pinfunction "6_6") (pintype "passive"))
      (node (ref "U9") (pin "23") (pinfunction "RXP_23") (pintype "passive"))
    )
    (net (code "139") (name "Net-(U9-TXN)") (class "Default")
      (node (ref "R12") (pin "1") (pinfunction "1_1") (pintype "passive"))
      (node (ref "T1") (pin "3") (pinfunction "3_3") (pintype "passive"))
      (node (ref "U9") (pin "20") (pinfunction "TXN_20") (pintype "passive"))
    )
    (net (code "140") (name "Net-(U9-TXP)") (class "Default")
      (node (ref "R11") (pin "1") (pinfunction "1_1") (pintype "passive"))
      (node (ref "T1") (pin "1") (pinfunction "1_1") (pintype "passive"))
      (node (ref "U9") (pin "21") (pinfunction "TXP_21") (pintype "passive"))
    )
    (net (code "141") (name "Net-(U9-VDD1A)") (class "Default")
      (node (ref "C27") (pin "2") (pinfunction "2_2") (pintype "passive"))
      (node (ref "C28") (pin "2") (pinfunction "2_2") (pintype "passive"))
      (node (ref "C29") (pin "2") (pinfunction "2_2") (pintype "passive"))
      (node (ref "I1") (pin "1") (pinfunction "1_1") (pintype "passive"))
      (node (ref "R11") (pin "2") (pinfunction "2_2") (pintype "passive"))
      (node (ref "R12") (pin "2") (pinfunction "2_2") (pintype "passive"))
      (node (ref "R13") (pin "2") (pinfunction "2_2") (pintype "passive"))
      (node (ref "R14") (pin "2") (pinfunction "2_2") (pintype "passive"))
      (node (ref "T1") (pin "2") (pinfunction "2_2") (pintype "passive"))
      (node (ref "T1") (pin "7") (pinfunction "7_7") (pintype "passive"))
      (node (ref "U9") (pin "1") (pinfunction "VDD2A_1") (pintype "passive"))
      (node (ref "U9") (pin "19") (pinfunction "VDD1A_19") (pintype "passive"))
    )
    (net (code "142") (name "Net-(U9-XTAL1{slash}CLKIN)") (class "Default")
      (node (ref "C31") (pin "1") (pinfunction "1_1") (pintype "passive"))
      (node (ref "U9") (pin "5") (pinfunction "XTAL1/CLKIN_5") (pintype "passive"))
      (node (ref "Y3") (pin "2") (pinfunction "OSC2_2") (pintype "passive"))
    )
    (net (code "143") (name "Net-(U9-XTAL2)") (class "Default")
      (node (ref "C32") (pin "1") (pinfunction "1_1") (pintype "passive"))
      (node (ref "U9") (pin "4") (pinfunction "XTAL2_4") (pintype "passive"))
      (node (ref "Y3") (pin "1") (pinfunction "OSC1_1") (pintype "passive"))
    )
    (net (code "144") (name "Net-(U9-nRST)") (class "Default")
      (node (ref "R16") (pin "1") (pinfunction "1_1") (pintype "passive"))
      (node (ref "U9") (pin "15") (pinfunction "nRST_15") (pintype "passive"))
    )
    (net (code "145") (name "PE") (class "Default")
      (node (ref "C33") (pin "2") (pinfunction "2_2") (pintype "passive"))
      (node (ref "P14") (pin "13") (pinfunction "NC_13") (pintype "passive"))
      (node (ref "P14") (pin "14") (pinfunction "NC_14") (pintype "passive"))
    )
    (net (code "146") (name "unconnected-(P1-NC-Pad3)") (class "Default")
      (node (ref "P1") (pin "3") (pinfunction "NC_3") (pintype "passive+no_connect"))
    )
    (net (code "147") (name "unconnected-(P6-NC-Pad5)") (class "Default")
      (node (ref "P6") (pin "5") (pinfunction "NC_5") (pintype "passive+no_connect"))
    )
    (net (code "148") (name "unconnected-(P14-Pad4)") (class "Default")
      (node (ref "P14") (pin "4") (pintype "passive+no_connect"))
    )
    (net (code "149") (name "unconnected-(P14-Pad5)") (class "Default")
      (node (ref "P14") (pin "5") (pintype "passive+no_connect"))
    )
    (net (code "150") (name "unconnected-(P14-Pad7)") (class "Default")
      (node (ref "P14") (pin "7") (pintype "passive+no_connect"))
    )
    (net (code "151") (name "unconnected-(P14-Pad8)") (class "Default")
      (node (ref "P14") (pin "8") (pintype "passive+no_connect"))
    )
    (net (code "152") (name "unconnected-(U3-PA0-WKUP(PA0){slash}USART2_CTS{slash}UART4_TX{slash}ETH_MII_CRS{slash}TIM2_CH1_ETR{slash}TIM5_CH1{slash}TIM8_ETR{slash}EVENTOUT{slash}ADC123_IN0{slash}WKUP-Pad34)") (class "Default")
      (node (ref "U3") (pin "34") (pinfunction "PA0-WKUP(PA0)/USART2_CTS/UART4_TX/ETH_MII_CRS/TIM2_CH1_ETR/TIM5_CH1/TIM8_ETR/EVENTOUT/ADC123_IN0/WKUP_34") (pintype "bidirectional"))
    )
    (net (code "153") (name "unconnected-(U3-PA3{slash}USART2_RX{slash}TIM5_CH4{slash}TIM9_CH2{slash}TIM2_CH4{slash}OTG_HS_ULPI_D0{slash}ETH_MII_COL{slash}EVENTOUT{slash}ADC123_IN3-Pad37)") (class "Default")
      (node (ref "U3") (pin "37") (pinfunction "PA3/USART2_RX/TIM5_CH4/TIM9_CH2/TIM2_CH4/OTG_HS_ULPI_D0/ETH_MII_COL/EVENTOUT/ADC123_IN3_37") (pintype "bidirectional"))
    )
    (net (code "154") (name "unconnected-(U3-PA4{slash}SPI1_NSS{slash}SPI3_NSS{slash}USART2_CK{slash}DCMI_HSYNC{slash}OTG_HS_SOF{slash}I2S3_WS{slash}EVENTOUT{slash}ADC12_IN4{slash}DAC1_OUT-Pad40)") (class "Default")
      (node (ref "U3") (pin "40") (pinfunction "PA4/SPI1_NSS/SPI3_NSS/USART2_CK/DCMI_HSYNC/OTG_HS_SOF/I2S3_WS/EVENTOUT/ADC12_IN4/DAC1_OUT_40") (pintype "bidirectional"))
    )
    (net (code "155") (name "unconnected-(U3-PA5{slash}SPI1_SCK{slash}OTG_HS_ULPI_CK{slash}TIM2_CH1_ETR{slash}TIM8_CHIN{slash}EVENTOUT{slash}ADC12_IN5{slash}DAC2_OUT-Pad41)") (class "Default")
      (node (ref "U3") (pin "41") (pinfunction "PA5/SPI1_SCK/OTG_HS_ULPI_CK/TIM2_CH1_ETR/TIM8_CHIN/EVENTOUT/ADC12_IN5/DAC2_OUT_41") (pintype "bidirectional"))
    )
    (net (code "156") (name "unconnected-(U3-PA6{slash}SPI1_MISO{slash}TIM8_BKIN{slash}TIM13_CH1{slash}DCMI_PIXCLK{slash}TIM3_CH1{slash}TIM1_BKIN{slash}EVENTOUT{slash}ADC12_IN6-Pad42)") (class "Default")
      (node (ref "U3") (pin "42") (pinfunction "PA6/SPI1_MISO/TIM8_BKIN/TIM13_CH1/DCMI_PIXCLK/TIM3_CH1/TIM1_BKIN/EVENTOUT/ADC12_IN6_42") (pintype "bidirectional"))
    )
    (net (code "157") (name "unconnected-(U3-PB0{slash}TIM3_CH3{slash}TIM8_CH2N{slash}OTG_HS_ULPI_D1{slash}ETH_MII_RXD2{slash}TIM1_CH2N{slash}EVENTOUT{slash}ADC12_IN8-Pad46)") (class "Default")
      (node (ref "U3") (pin "46") (pinfunction "PB0/TIM3_CH3/TIM8_CH2N/OTG_HS_ULPI_D1/ETH_MII_RXD2/TIM1_CH2N/EVENTOUT/ADC12_IN8_46") (pintype "bidirectional"))
    )
    (net (code "158") (name "unconnected-(U3-PB1{slash}TIM3_CH4{slash}TIM8_CH3N{slash}OTG_HS_ULPI_D2{slash}ETH_MII_RXD3{slash}OTG_HS_INTN{slash}TIM1_CH3N{slash}EVENTOUT{slash}ADC12_IN9-Pad47)") (class "Default")
      (node (ref "U3") (pin "47") (pinfunction "PB1/TIM3_CH4/TIM8_CH3N/OTG_HS_ULPI_D2/ETH_MII_RXD3/OTG_HS_INTN/TIM1_CH3N/EVENTOUT/ADC12_IN9_47") (pintype "bidirectional"))
    )
    (net (code "159") (name "unconnected-(U3-PB14{slash}SPI2_MISO{slash}TIM1_CH2N{slash}TIM12_CH1{slash}OTG_HS_DM{slash}USART3_RTS{slash}TIM8_CH2N{slash}I2S2ext_SD{slash}EVENTOUT-Pad75)") (class "Default")
      (node (ref "U3") (pin "75") (pinfunction "PB14/SPI2_MISO/TIM1_CH2N/TIM12_CH1/OTG_HS_DM/USART3_RTS/TIM8_CH2N/I2S2ext_SD/EVENTOUT_75") (pintype "bidirectional"))
    )
    (net (code "160") (name "unconnected-(U3-PB15{slash}SPI2_MOSI{slash}I2S2_SD{slash}TIM1_CH3N{slash}TIM8_CH3N{slash}TIM12_CH2{slash}OTG_HS_DP{slash}EVENTOUT-Pad76)") (class "Default")
      (node (ref "U3") (pin "76") (pinfunction "PB15/SPI2_MOSI/I2S2_SD/TIM1_CH3N/TIM8_CH3N/TIM12_CH2/OTG_HS_DP/EVENTOUT_76") (pintype "bidirectional"))
    )
    (net (code "161") (name "unconnected-(U3-PC0{slash}OTG_HS_ULPI_STP{slash}EVENTOUT{slash}ADC123_IN10-Pad26)") (class "Default")
      (node (ref "U3") (pin "26") (pinfunction "PC0/OTG_HS_ULPI_STP/EVENTOUT/ADC123_IN10_26") (pintype "bidirectional"))
    )
    (net (code "162") (name "unconnected-(U3-PC2{slash}SPI2_MISO{slash}OTG_HS_ULPI_DIR{slash}TH_MII_TXD2{slash}I2S2ext_SD{slash}EVENTOUT{slash}ADC123_IN12-Pad28)") (class "Default")
      (node (ref "U3") (pin "28") (pinfunction "PC2/SPI2_MISO/OTG_HS_ULPI_DIR/TH_MII_TXD2/I2S2ext_SD/EVENTOUT/ADC123_IN12_28") (pintype "bidirectional"))
    )
    (net (code "163") (name "unconnected-(U3-PC3{slash}SPI2_MOSI{slash}I2S2_SD{slash}OTG_HS_ULPI_NXT{slash}ETH_MII_TX_CLK{slash}EVENTOUT{slash}ADC123_IN13-Pad29)") (class "Default")
      (node (ref "U3") (pin "29") (pinfunction "PC3/SPI2_MOSI/I2S2_SD/OTG_HS_ULPI_NXT/ETH_MII_TX_CLK/EVENTOUT/ADC123_IN13_29") (pintype "bidirectional"))
    )
    (net (code "164") (name "unconnected-(U3-PC13{slash}EVENTOUT{slash}RTC_AF1-Pad7)") (class "Default")
      (node (ref "U3") (pin "7") (pinfunction "PC13/EVENTOUT/RTC_AF1_7") (pintype "bidirectional"))
    )
    (net (code "165") (name "unconnected-(U3-PD6{slash}FSMC_NWAIT{slash}USART2_RX{slash}EVENTOUT-Pad122)") (class "Default")
      (node (ref "U3") (pin "122") (pinfunction "PD6/FSMC_NWAIT/USART2_RX/EVENTOUT_122") (pintype "bidirectional"))
    )
    (net (code "166") (name "unconnected-(U3-PD7{slash}USART2_CK{slash}FSMC_NE1{slash}FSMC_NCE2{slash}EVENTOUT-Pad123)") (class "Default")
      (node (ref "U3") (pin "123") (pinfunction "PD7/USART2_CK/FSMC_NE1/FSMC_NCE2/EVENTOUT_123") (pintype "bidirectional"))
    )
    (net (code "167") (name "unconnected-(U3-PE2{slash}TRACECLK{slash}FSMC_A23{slash}ETH_MII_TXD3{slash}EVENTOUT-Pad1)") (class "Default")
      (node (ref "U3") (pin "1") (pinfunction "PE2/TRACECLK/FSMC_A23/ETH_MII_TXD3/EVENTOUT_1") (pintype "bidirectional"))
    )
    (net (code "168") (name "unconnected-(U3-PE3{slash}TRACED0{slash}FSMC_A19{slash}EVENTOUT-Pad2)") (class "Default")
      (node (ref "U3") (pin "2") (pinfunction "PE3/TRACED0/FSMC_A19/EVENTOUT_2") (pintype "bidirectional"))
    )
    (net (code "169") (name "unconnected-(U3-PE4{slash}TRACED1{slash}FSMC_A20{slash}DCMI_D4{slash}EVENTOUT-Pad3)") (class "Default")
      (node (ref "U3") (pin "3") (pinfunction "PE4/TRACED1/FSMC_A20/DCMI_D4/EVENTOUT_3") (pintype "bidirectional"))
    )
    (net (code "170") (name "unconnected-(U3-PE5{slash}TRACED2{slash}FSMC_A21{slash}TIM9_CH1{slash}DCMI_D6{slash}EVENTOUT-Pad4)") (class "Default")
      (node (ref "U3") (pin "4") (pinfunction "PE5/TRACED2/FSMC_A21/TIM9_CH1/DCMI_D6/EVENTOUT_4") (pintype "bidirectional"))
    )
    (net (code "171") (name "unconnected-(U3-PE6{slash}TRACED3{slash}FSMC_A22{slash}TIM9_CH2{slash}DCMI_D7{slash}EVENTOUT-Pad5)") (class "Default")
      (node (ref "U3") (pin "5") (pinfunction "PE6/TRACED3/FSMC_A22/TIM9_CH2/DCMI_D7/EVENTOUT_5") (pintype "bidirectional"))
    )
    (net (code "172") (name "unconnected-(U3-PF6{slash}TIM10_CH1{slash}FSMC_NIORD{slash}EVENTOUT{slash}ADC3_IN4-Pad18)") (class "Default")
      (node (ref "U3") (pin "18") (pinfunction "PF6/TIM10_CH1/FSMC_NIORD/EVENTOUT/ADC3_IN4_18") (pintype "bidirectional"))
    )
    (net (code "173") (name "unconnected-(U3-PF7{slash}TIM11_CH1{slash}FSMC_NREG{slash}EVENTOUT{slash}ADC3_IN5-Pad19)") (class "Default")
      (node (ref "U3") (pin "19") (pinfunction "PF7/TIM11_CH1/FSMC_NREG/EVENTOUT/ADC3_IN5_19") (pintype "bidirectional"))
    )
    (net (code "174") (name "unconnected-(U3-PF8{slash}TIM13_CH1{slash}FSMC_NIOWR{slash}EVENTOUT{slash}ADC3_IN6-Pad20)") (class "Default")
      (node (ref "U3") (pin "20") (pinfunction "PF8/TIM13_CH1/FSMC_NIOWR/EVENTOUT/ADC3_IN6_20") (pintype "bidirectional"))
    )
    (net (code "175") (name "unconnected-(U3-PF9{slash}TIM14_CH1{slash}FSMC_CD{slash}EVENTOUT{slash}ADC3_IN7-Pad21)") (class "Default")
      (node (ref "U3") (pin "21") (pinfunction "PF9/TIM14_CH1/FSMC_CD/EVENTOUT/ADC3_IN7_21") (pintype "bidirectional"))
    )
    (net (code "176") (name "unconnected-(U3-PF10{slash}FSMC_INTR{slash}EVENTOUT{slash}ADC3_IN8-Pad22)") (class "Default")
      (node (ref "U3") (pin "22") (pinfunction "PF10/FSMC_INTR/EVENTOUT/ADC3_IN8_22") (pintype "bidirectional"))
    )
    (net (code "177") (name "unconnected-(U3-PG6{slash}FSMC_INT2{slash}EVENTOUT-Pad91)") (class "Default")
      (node (ref "U3") (pin "91") (pinfunction "PG6/FSMC_INT2/EVENTOUT_91") (pintype "bidirectional"))
    )
    (net (code "178") (name "unconnected-(U3-PG9{slash}USART6_RX{slash}FSMC_NE2{slash}FSMC_NCE3{slash}EVENTOUT-Pad124)") (class "Default")
      (node (ref "U3") (pin "124") (pinfunction "PG9/USART6_RX/FSMC_NE2/FSMC_NCE3/EVENTOUT_124") (pintype "bidirectional"))
    )
    (net (code "179") (name "unconnected-(U3-PG12{slash}FSMC_NE4{slash}USART6_RTS{slash}EVENTOUT-Pad127)") (class "Default")
      (node (ref "U3") (pin "127") (pinfunction "PG12/FSMC_NE4/USART6_RTS/EVENTOUT_127") (pintype "bidirectional"))
    )
    (net (code "180") (name "unconnected-(U5-R1IN-Pad13)") (class "Default")
      (node (ref "U5") (pin "13") (pinfunction "R1IN_13") (pintype "passive"))
    )
    (net (code "181") (name "unconnected-(U5-R1OUT-Pad12)") (class "Default")
      (node (ref "U5") (pin "12") (pinfunction "R1OUT_12") (pintype "passive"))
    )
    (net (code "182") (name "unconnected-(U5-T1IN-Pad11)") (class "Default")
      (node (ref "U5") (pin "11") (pinfunction "T1IN_11") (pintype "passive"))
    )
    (net (code "183") (name "unconnected-(U5-T1OUT-Pad14)") (class "Default")
      (node (ref "U5") (pin "14") (pinfunction "T1OUT_14") (pintype "passive"))
    )
  )
)
